# io-board-b-2.net
KiCad netlist of a schematic drawn in EAGLE
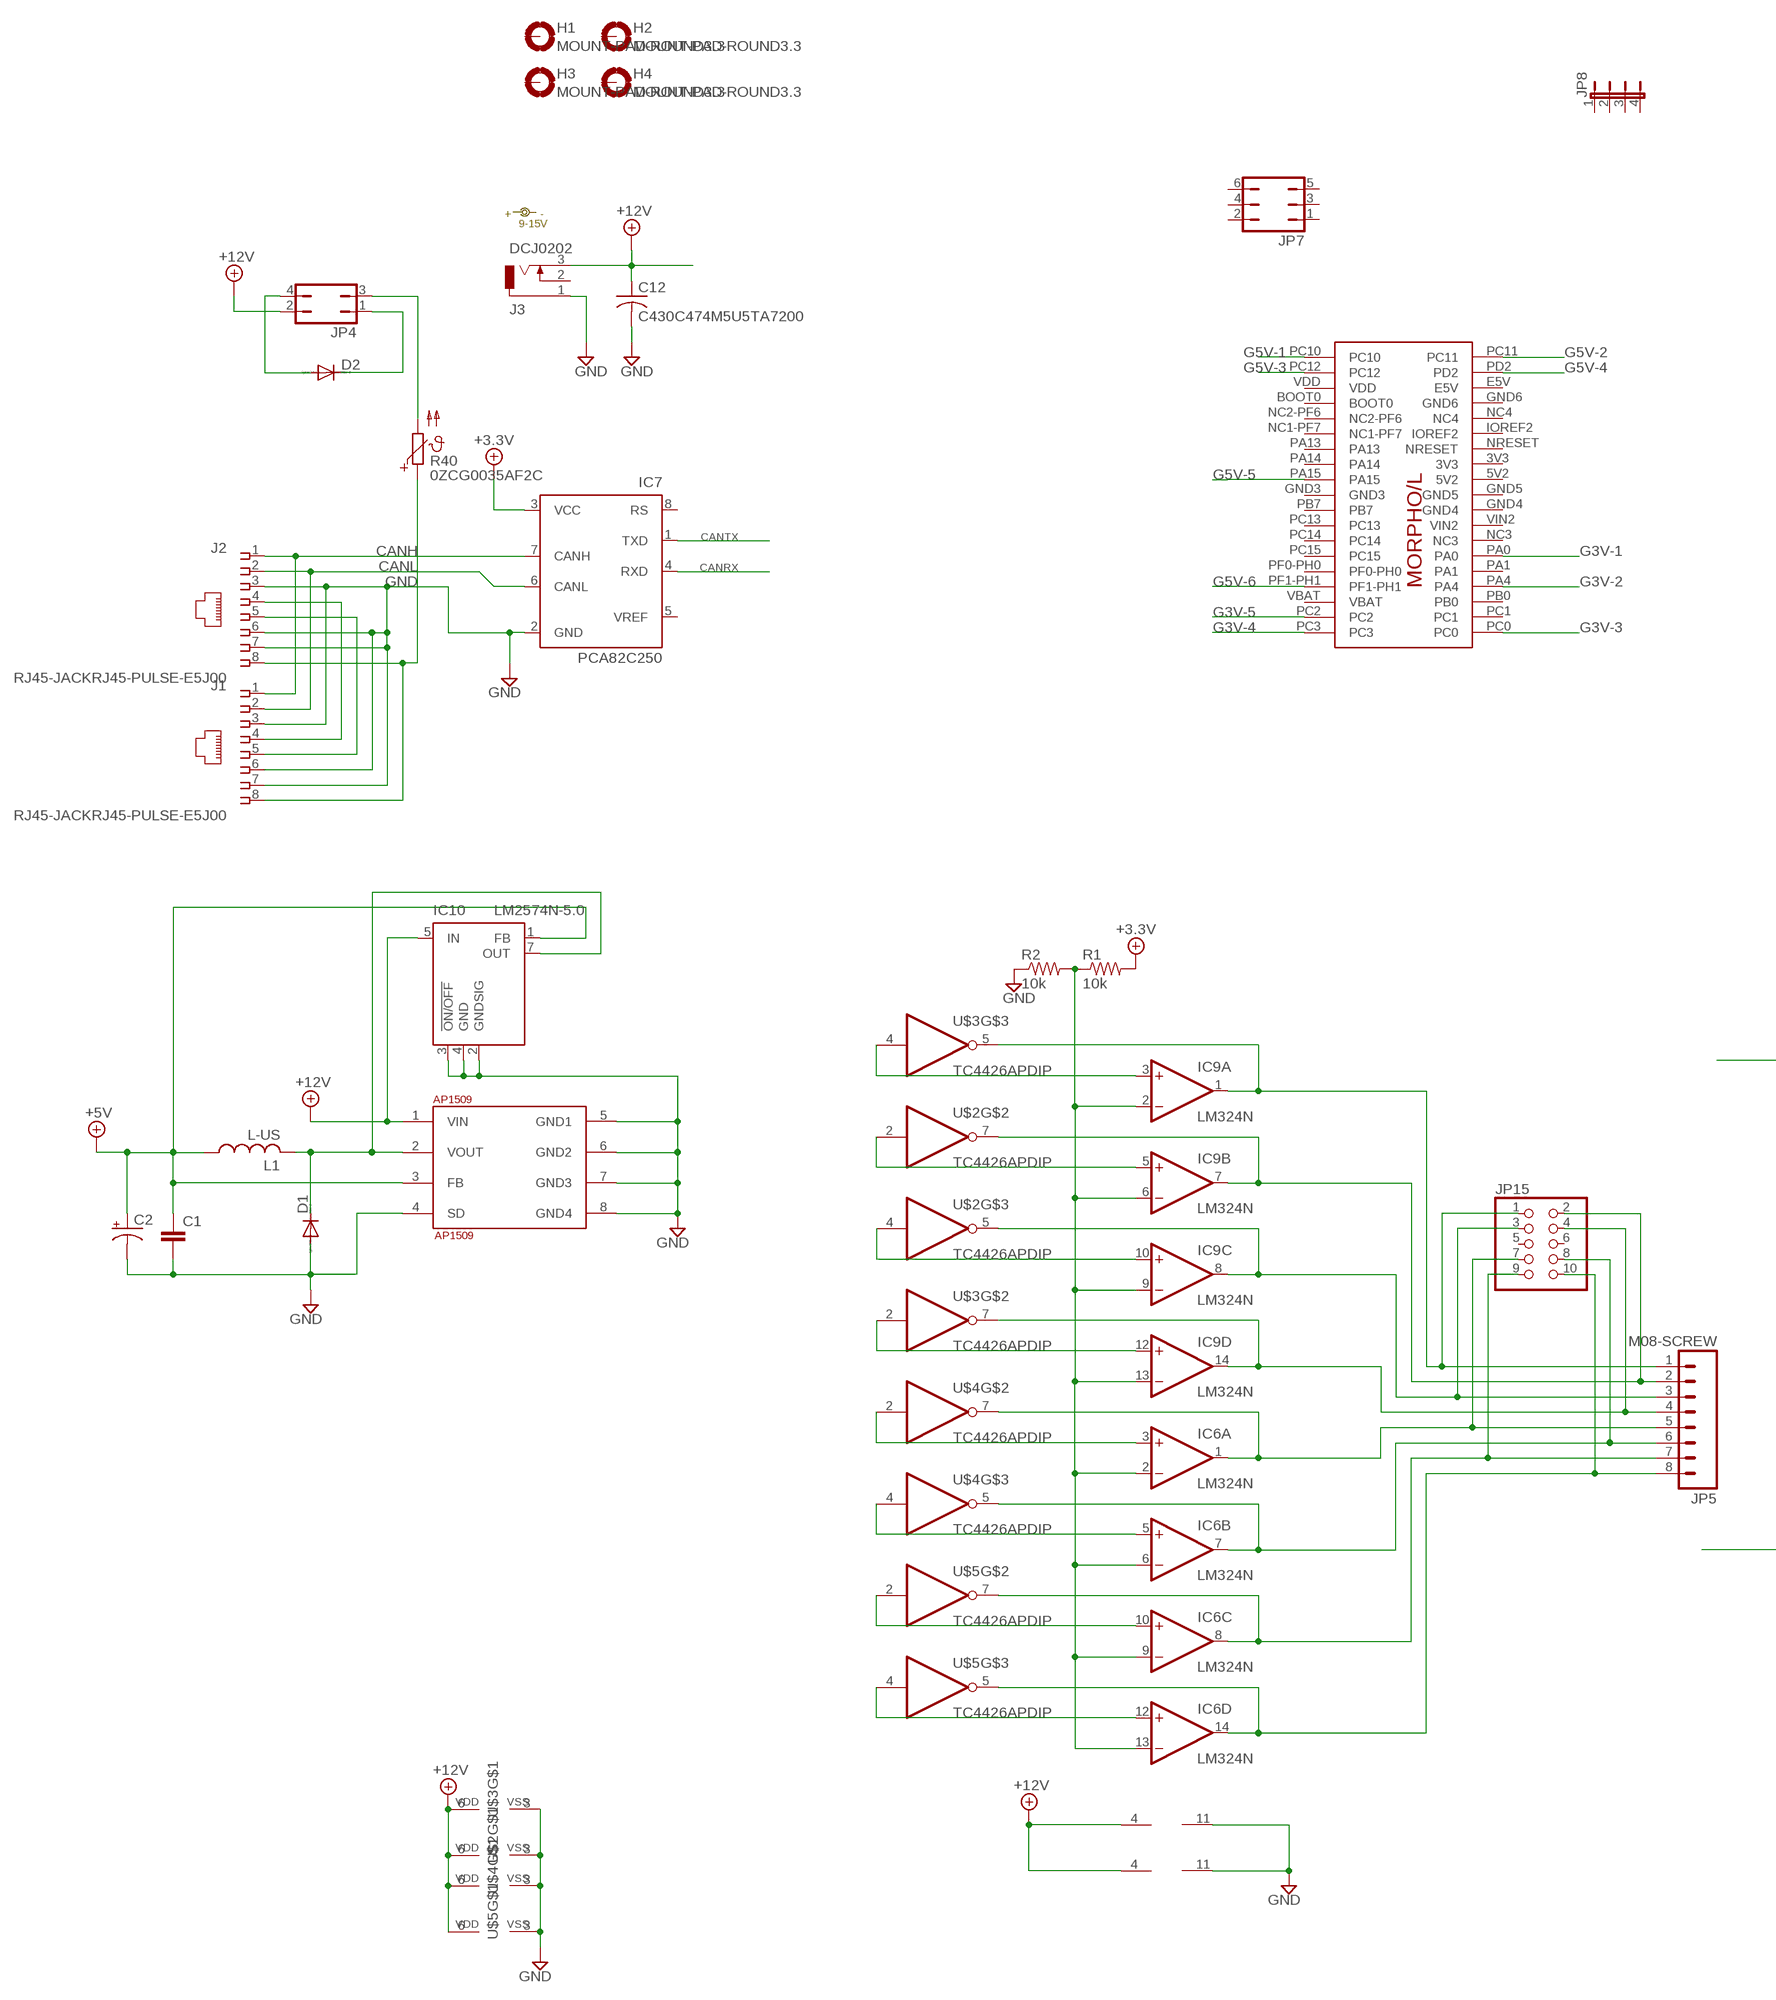
[diagram p0: schematic, sheet 1, part 1 of 2]
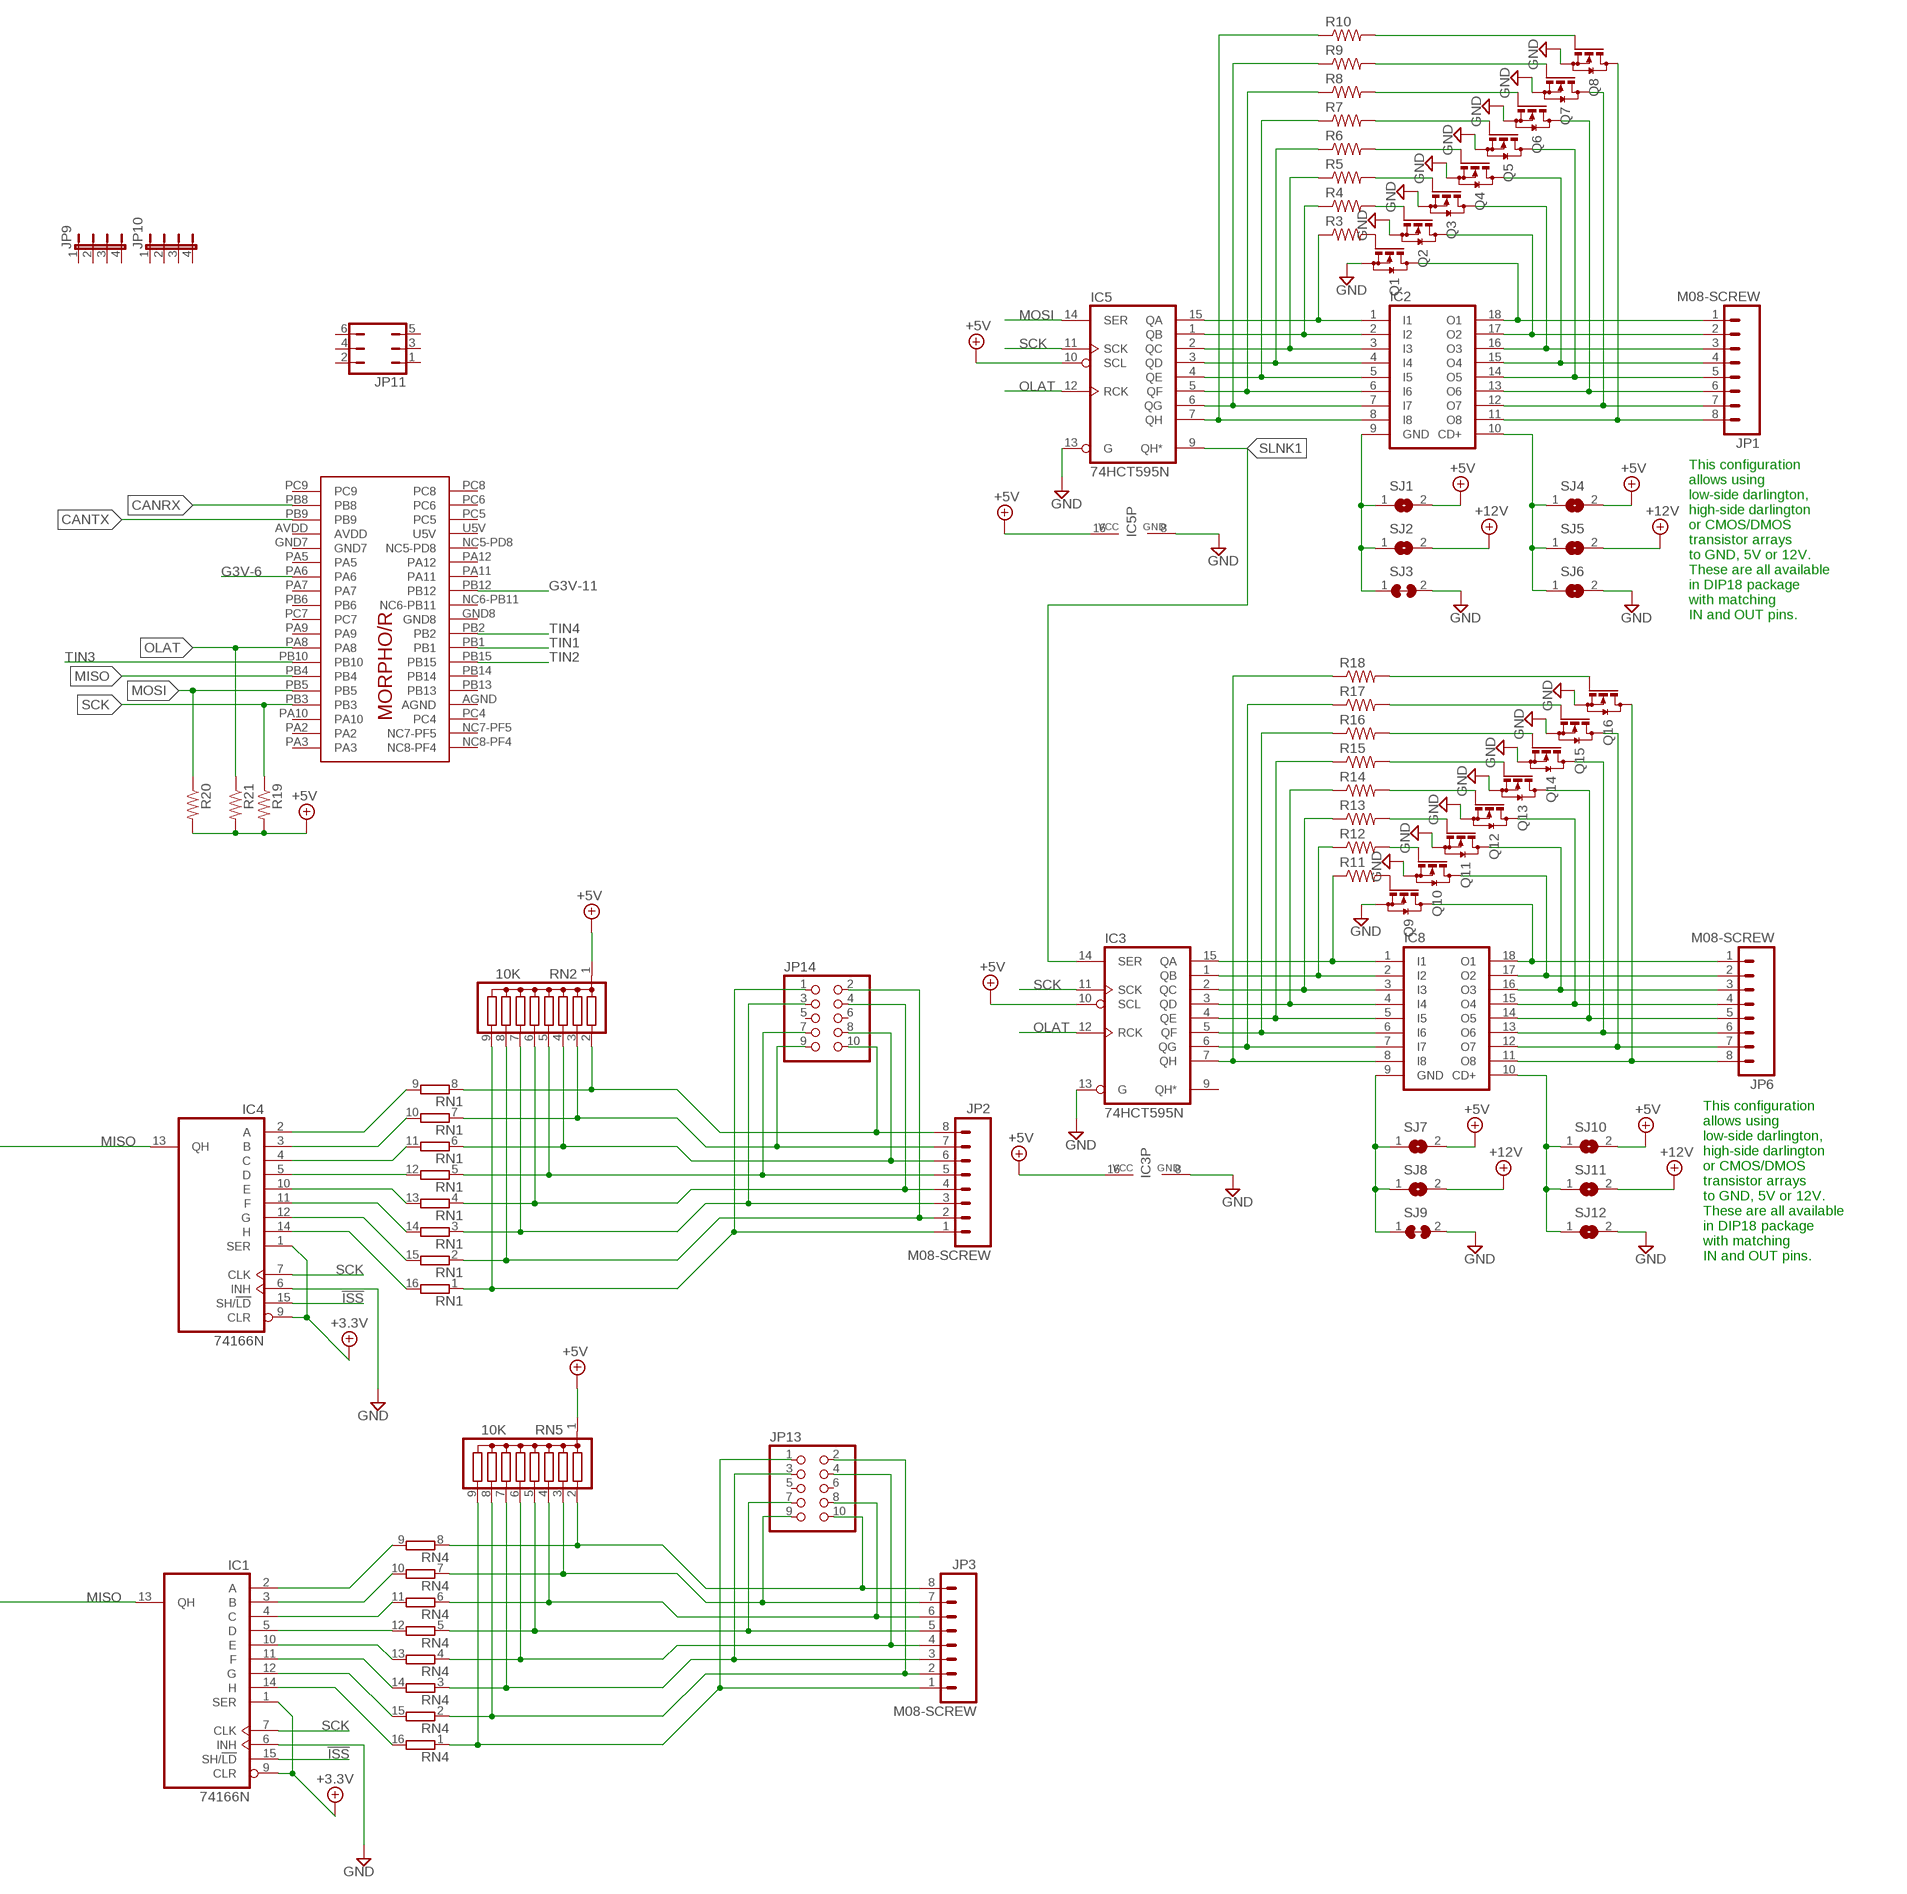
[diagram p1: schematic, sheet 1, part 2 of 2]

(export (version "E")
  (design (tool "Eeschema 10.0.6"))
  (components
    (comp (ref "+12V")
      (value "9-15V")
      (footprint "eagle-import:POWER_USAGE")
      (libsource (lib "eagle-import") (part "DOC-POWER_LABEL"))
    )
    (comp (ref "AP1509")
      (value "AP1509")
      (footprint "eagle-import:SO-08")
      (libsource (lib "eagle-import") (part "AP1509"))
    )
    (comp (ref "C1")
      (value "C-EUC1206")
      (footprint "eagle-import:C1206")
      (libsource (lib "eagle-import") (part "C-EUC1206"))
    )
    (comp (ref "C2")
      (value "CPOL-USE2.5-5")
      (footprint "eagle-import:E2,5-5")
      (libsource (lib "eagle-import") (part "CPOL-USE2.5-5"))
    )
    (comp (ref "C12")
      (value "C430C474M5U5TA7200")
      (footprint "eagle-import:C075-032X103")
      (libsource (lib "eagle-import") (part "C-US075-032X103"))
    )
    (comp (ref "D1")
      (value "DIODE-DO41-7.6")
      (footprint "eagle-import:DO41-7.6")
      (libsource (lib "eagle-import") (part "DIODE-DO41-7.6"))
    )
    (comp (ref "D2")
      (value "DIODE-DO41-7.6")
      (footprint "eagle-import:DO41-7.6")
      (libsource (lib "eagle-import") (part "DIODE-DO41-7.6"))
    )
    (comp (ref "H1")
      (value "MOUNT-PAD-ROUND3.3")
      (footprint "eagle-import:3,3-PAD")
      (libsource (lib "eagle-import") (part "MOUNT-PAD-ROUND3.3"))
    )
    (comp (ref "H2")
      (value "MOUNT-PAD-ROUND3.3")
      (footprint "eagle-import:3,3-PAD")
      (libsource (lib "eagle-import") (part "MOUNT-PAD-ROUND3.3"))
    )
    (comp (ref "H3")
      (value "MOUNT-PAD-ROUND3.3")
      (footprint "eagle-import:3,3-PAD")
      (libsource (lib "eagle-import") (part "MOUNT-PAD-ROUND3.3"))
    )
    (comp (ref "H4")
      (value "MOUNT-PAD-ROUND3.3")
      (footprint "eagle-import:3,3-PAD")
      (libsource (lib "eagle-import") (part "MOUNT-PAD-ROUND3.3"))
    )
    (comp (ref "IC1")
      (value "74166N")
      (footprint "eagle-import:DIL16")
      (libsource (lib "eagle-import") (part "74166N"))
    )
    (comp (ref "IC2")
      (value "ULN2803A")
      (footprint "eagle-import:DIL18-THIN")
      (libsource (lib "eagle-import") (part "ULN2803A"))
    )
    (comp (ref "IC3")
      (value "74HCT595N")
      (footprint "eagle-import:DIL16")
      (libsource (lib "eagle-import") (part "74595NHCT"))
    )
    (comp (ref "IC4")
      (value "74166N")
      (footprint "eagle-import:DIL16")
      (libsource (lib "eagle-import") (part "74166N"))
    )
    (comp (ref "IC5")
      (value "74HCT595N")
      (footprint "eagle-import:DIL16")
      (libsource (lib "eagle-import") (part "74595NHCT"))
    )
    (comp (ref "IC6")
      (value "LM324N")
      (footprint "eagle-import:DIL14")
      (libsource (lib "eagle-import") (part "LM324N"))
    )
    (comp (ref "IC7")
      (value "PCA82C250")
      (footprint "eagle-import:DIL08")
      (libsource (lib "eagle-import") (part "PCA82C250"))
    )
    (comp (ref "IC8")
      (value "ULN2803A")
      (footprint "eagle-import:DIL18-THIN")
      (libsource (lib "eagle-import") (part "ULN2803A"))
    )
    (comp (ref "IC9")
      (value "LM324N")
      (footprint "eagle-import:DIL14")
      (libsource (lib "eagle-import") (part "LM324N"))
    )
    (comp (ref "IC10")
      (value "LM2574N-5.0")
      (footprint "eagle-import:DIL08")
      (libsource (lib "eagle-import") (part "LM2574?-N5.0"))
    )
    (comp (ref "J1")
      (value "RJ45-JACKRJ45-PULSE-E5J00")
      (footprint "eagle-import:RJ45-PULSE-E5J88")
      (libsource (lib "eagle-import") (part "RJ45-JACKRJ45-PULSE-E5J00"))
    )
    (comp (ref "J2")
      (value "RJ45-JACKRJ45-PULSE-E5J00")
      (footprint "eagle-import:RJ45-PULSE-E5J88")
      (libsource (lib "eagle-import") (part "RJ45-JACKRJ45-PULSE-E5J00"))
    )
    (comp (ref "J3")
      (value "DCJ0202")
      (footprint "eagle-import:DCJ0202")
      (libsource (lib "eagle-import") (part "DCJ0202"))
    )
    (comp (ref "JP1")
      (value "M08-SCREW")
      (footprint "eagle-import:1X08_TERMINAL")
      (libsource (lib "eagle-import") (part "M08-SCREW"))
    )
    (comp (ref "JP2")
      (value "M08-SCREW")
      (footprint "eagle-import:1X08_TERMINAL")
      (libsource (lib "eagle-import") (part "M08-SCREW"))
    )
    (comp (ref "JP3")
      (value "M08-SCREW")
      (footprint "eagle-import:1X08_TERMINAL")
      (libsource (lib "eagle-import") (part "M08-SCREW"))
    )
    (comp (ref "JP4")
      (value "JP2Q")
      (footprint "eagle-import:JP2Q")
      (libsource (lib "eagle-import") (part "JP2Q"))
    )
    (comp (ref "JP5")
      (value "M08-SCREW")
      (footprint "eagle-import:1X08_TERMINAL")
      (libsource (lib "eagle-import") (part "M08-SCREW"))
    )
    (comp (ref "JP6")
      (value "M08-SCREW")
      (footprint "eagle-import:1X08_TERMINAL")
      (libsource (lib "eagle-import") (part "M08-SCREW"))
    )
    (comp (ref "JP7")
      (value "JP3Q")
      (footprint "eagle-import:JP3Q")
      (libsource (lib "eagle-import") (part "JP3Q"))
    )
    (comp (ref "JP8")
      (value "JP4-FLAT")
      (footprint "eagle-import:JP4F")
      (libsource (lib "eagle-import") (part "JP4-FLAT"))
    )
    (comp (ref "JP9")
      (value "JP4-FLAT")
      (footprint "eagle-import:JP4F")
      (libsource (lib "eagle-import") (part "JP4-FLAT"))
    )
    (comp (ref "JP10")
      (value "JP4-FLAT")
      (footprint "eagle-import:JP4F")
      (libsource (lib "eagle-import") (part "JP4-FLAT"))
    )
    (comp (ref "JP11")
      (value "JP3Q")
      (footprint "eagle-import:JP3Q")
      (libsource (lib "eagle-import") (part "JP3Q"))
    )
    (comp (ref "JP13")
      (value "PINHD-2X5CN")
      (footprint "eagle-import:CON10M")
      (libsource (lib "eagle-import") (part "PINHD-2X5CN"))
    )
    (comp (ref "JP14")
      (value "PINHD-2X5CN")
      (footprint "eagle-import:CON10M")
      (libsource (lib "eagle-import") (part "PINHD-2X5CN"))
    )
    (comp (ref "JP15")
      (value "PINHD-2X5CN")
      (footprint "eagle-import:CON10M")
      (libsource (lib "eagle-import") (part "PINHD-2X5CN"))
    )
    (comp (ref "L1")
      (value "L-US")
      (footprint "eagle-import:L5-8,5")
      (libsource (lib "eagle-import") (part "L-US"))
    )
    (comp (ref "Q1")
      (value "BSS123")
      (footprint "eagle-import:SOT23")
      (libsource (lib "eagle-import") (part "BSS123"))
    )
    (comp (ref "Q2")
      (value "BSS123")
      (footprint "eagle-import:SOT23")
      (libsource (lib "eagle-import") (part "BSS123"))
    )
    (comp (ref "Q3")
      (value "BSS123")
      (footprint "eagle-import:SOT23")
      (libsource (lib "eagle-import") (part "BSS123"))
    )
    (comp (ref "Q4")
      (value "BSS123")
      (footprint "eagle-import:SOT23")
      (libsource (lib "eagle-import") (part "BSS123"))
    )
    (comp (ref "Q5")
      (value "BSS123")
      (footprint "eagle-import:SOT23")
      (libsource (lib "eagle-import") (part "BSS123"))
    )
    (comp (ref "Q6")
      (value "BSS123")
      (footprint "eagle-import:SOT23")
      (libsource (lib "eagle-import") (part "BSS123"))
    )
    (comp (ref "Q7")
      (value "BSS123")
      (footprint "eagle-import:SOT23")
      (libsource (lib "eagle-import") (part "BSS123"))
    )
    (comp (ref "Q8")
      (value "BSS123")
      (footprint "eagle-import:SOT23")
      (libsource (lib "eagle-import") (part "BSS123"))
    )
    (comp (ref "Q9")
      (value "BSS123")
      (footprint "eagle-import:SOT23")
      (libsource (lib "eagle-import") (part "BSS123"))
    )
    (comp (ref "Q10")
      (value "BSS123")
      (footprint "eagle-import:SOT23")
      (libsource (lib "eagle-import") (part "BSS123"))
    )
    (comp (ref "Q11")
      (value "BSS123")
      (footprint "eagle-import:SOT23")
      (libsource (lib "eagle-import") (part "BSS123"))
    )
    (comp (ref "Q12")
      (value "BSS123")
      (footprint "eagle-import:SOT23")
      (libsource (lib "eagle-import") (part "BSS123"))
    )
    (comp (ref "Q13")
      (value "BSS123")
      (footprint "eagle-import:SOT23")
      (libsource (lib "eagle-import") (part "BSS123"))
    )
    (comp (ref "Q14")
      (value "BSS123")
      (footprint "eagle-import:SOT23")
      (libsource (lib "eagle-import") (part "BSS123"))
    )
    (comp (ref "Q15")
      (value "BSS123")
      (footprint "eagle-import:SOT23")
      (libsource (lib "eagle-import") (part "BSS123"))
    )
    (comp (ref "Q16")
      (value "BSS123")
      (footprint "eagle-import:SOT23")
      (libsource (lib "eagle-import") (part "BSS123"))
    )
    (comp (ref "R1")
      (value "10k")
      (footprint "eagle-import:R1206")
      (libsource (lib "eagle-import") (part "R-US_R1206"))
    )
    (comp (ref "R2")
      (value "10k")
      (footprint "eagle-import:R1206")
      (libsource (lib "eagle-import") (part "R-US_R1206"))
    )
    (comp (ref "R3")
      (value "R-US_R0603")
      (footprint "eagle-import:R0603")
      (libsource (lib "eagle-import") (part "R-US_R0603"))
    )
    (comp (ref "R4")
      (value "R-US_R0603")
      (footprint "eagle-import:R0603")
      (libsource (lib "eagle-import") (part "R-US_R0603"))
    )
    (comp (ref "R5")
      (value "R-US_R0603")
      (footprint "eagle-import:R0603")
      (libsource (lib "eagle-import") (part "R-US_R0603"))
    )
    (comp (ref "R6")
      (value "R-US_R0603")
      (footprint "eagle-import:R0603")
      (libsource (lib "eagle-import") (part "R-US_R0603"))
    )
    (comp (ref "R7")
      (value "R-US_R0603")
      (footprint "eagle-import:R0603")
      (libsource (lib "eagle-import") (part "R-US_R0603"))
    )
    (comp (ref "R8")
      (value "R-US_R0603")
      (footprint "eagle-import:R0603")
      (libsource (lib "eagle-import") (part "R-US_R0603"))
    )
    (comp (ref "R9")
      (value "R-US_R0603")
      (footprint "eagle-import:R0603")
      (libsource (lib "eagle-import") (part "R-US_R0603"))
    )
    (comp (ref "R10")
      (value "R-US_R0603")
      (footprint "eagle-import:R0603")
      (libsource (lib "eagle-import") (part "R-US_R0603"))
    )
    (comp (ref "R11")
      (value "R-US_R0603")
      (footprint "eagle-import:R0603")
      (libsource (lib "eagle-import") (part "R-US_R0603"))
    )
    (comp (ref "R12")
      (value "R-US_R0603")
      (footprint "eagle-import:R0603")
      (libsource (lib "eagle-import") (part "R-US_R0603"))
    )
    (comp (ref "R13")
      (value "R-US_R0603")
      (footprint "eagle-import:R0603")
      (libsource (lib "eagle-import") (part "R-US_R0603"))
    )
    (comp (ref "R14")
      (value "R-US_R0603")
      (footprint "eagle-import:R0603")
      (libsource (lib "eagle-import") (part "R-US_R0603"))
    )
    (comp (ref "R15")
      (value "R-US_R0603")
      (footprint "eagle-import:R0603")
      (libsource (lib "eagle-import") (part "R-US_R0603"))
    )
    (comp (ref "R16")
      (value "R-US_R0603")
      (footprint "eagle-import:R0603")
      (libsource (lib "eagle-import") (part "R-US_R0603"))
    )
    (comp (ref "R17")
      (value "R-US_R0603")
      (footprint "eagle-import:R0603")
      (libsource (lib "eagle-import") (part "R-US_R0603"))
    )
    (comp (ref "R18")
      (value "R-US_R0603")
      (footprint "eagle-import:R0603")
      (libsource (lib "eagle-import") (part "R-US_R0603"))
    )
    (comp (ref "R19")
      (value "R-US_R0805")
      (footprint "eagle-import:R0805")
      (libsource (lib "eagle-import") (part "rcl_334_R-US_R0805"))
    )
    (comp (ref "R20")
      (value "R-US_R0805")
      (footprint "eagle-import:R0805")
      (libsource (lib "eagle-import") (part "rcl_334_R-US_R0805"))
    )
    (comp (ref "R21")
      (value "R-US_R0805")
      (footprint "eagle-import:R0805")
      (libsource (lib "eagle-import") (part "rcl_334_R-US_R0805"))
    )
    (comp (ref "R40")
      (value "0ZCG0035AF2C")
      (footprint "eagle-import:PTC1812")
      (libsource (lib "eagle-import") (part "PTC_1812"))
    )
    (comp (ref "RN1")
      (value "8R-P")
      (footprint "eagle-import:DIL16")
      (libsource (lib "eagle-import") (part "8R-P"))
    )
    (comp (ref "RN2")
      (value "10K")
      (footprint "eagle-import:SIL9")
      (libsource (lib "eagle-import") (part "G08R"))
    )
    (comp (ref "RN4")
      (value "8R-P")
      (footprint "eagle-import:DIL16")
      (libsource (lib "eagle-import") (part "8R-P"))
    )
    (comp (ref "RN5")
      (value "10K")
      (footprint "eagle-import:SIL9")
      (libsource (lib "eagle-import") (part "G08R"))
    )
    (comp (ref "SJ1")
      (value "SJ")
      (footprint "eagle-import:SJ-RND")
      (libsource (lib "eagle-import") (part "SJ"))
    )
    (comp (ref "SJ2")
      (value "SJ")
      (footprint "eagle-import:SJ-RND")
      (libsource (lib "eagle-import") (part "SJ"))
    )
    (comp (ref "SJ3")
      (value "SJ-C")
      (footprint "eagle-import:SJW-C")
      (libsource (lib "eagle-import") (part "SJ-C"))
    )
    (comp (ref "SJ4")
      (value "SJ")
      (footprint "eagle-import:SJ-RND")
      (libsource (lib "eagle-import") (part "SJ"))
    )
    (comp (ref "SJ5")
      (value "SJ")
      (footprint "eagle-import:SJ-RND")
      (libsource (lib "eagle-import") (part "SJ"))
    )
    (comp (ref "SJ6")
      (value "SJ")
      (footprint "eagle-import:SJ-RND")
      (libsource (lib "eagle-import") (part "SJ"))
    )
    (comp (ref "SJ7")
      (value "SJ")
      (footprint "eagle-import:SJ-RND")
      (libsource (lib "eagle-import") (part "SJ"))
    )
    (comp (ref "SJ8")
      (value "SJ")
      (footprint "eagle-import:SJ-RND")
      (libsource (lib "eagle-import") (part "SJ"))
    )
    (comp (ref "SJ9")
      (value "SJ-C")
      (footprint "eagle-import:SJW-C")
      (libsource (lib "eagle-import") (part "SJ-C"))
    )
    (comp (ref "SJ10")
      (value "SJ")
      (footprint "eagle-import:SJ-RND")
      (libsource (lib "eagle-import") (part "SJ"))
    )
    (comp (ref "SJ11")
      (value "SJ")
      (footprint "eagle-import:SJ-RND")
      (libsource (lib "eagle-import") (part "SJ"))
    )
    (comp (ref "SJ12")
      (value "SJ")
      (footprint "eagle-import:SJ-RND")
      (libsource (lib "eagle-import") (part "SJ"))
    )
    (comp (ref "U$1")
      (value "NUCLEO_64_GENERIC")
      (footprint "eagle-import:NUCLEO_BRD_BASE64")
      (libsource (lib "eagle-import") (part "NUCLEO_64_GENERIC"))
    )
    (comp (ref "U$2")
      (value "TC4426APDIP")
      (footprint "eagle-import:DIL08-LONG")
      (libsource (lib "eagle-import") (part "TC4426APDIP"))
    )
    (comp (ref "U$3")
      (value "TC4426APDIP")
      (footprint "eagle-import:DIL08-LONG")
      (libsource (lib "eagle-import") (part "TC4426APDIP"))
    )
    (comp (ref "U$4")
      (value "TC4426APDIP")
      (footprint "eagle-import:DIL08-LONG")
      (libsource (lib "eagle-import") (part "TC4426APDIP"))
    )
    (comp (ref "U$5")
      (value "TC4426APDIP")
      (footprint "eagle-import:DIL08-LONG")
      (libsource (lib "eagle-import") (part "TC4426APDIP"))
    )
  )
  (nets
    (net (code "1") (name "+3.3V") (class "Default")
      (node (ref "IC1") (pin "1") (pinfunction "SER_1") (pintype "input"))
      (node (ref "IC1") (pin "9") (pinfunction "CLR_9") (pintype "input"))
      (node (ref "IC4") (pin "1") (pinfunction "SER_1") (pintype "input"))
      (node (ref "IC4") (pin "9") (pinfunction "CLR_9") (pintype "input"))
      (node (ref "IC7") (pin "3") (pinfunction "VCC_3") (pintype "power_in"))
      (node (ref "R1") (pin "2") (pinfunction "2_2") (pintype "passive"))
    )
    (net (code "2") (name "+5V") (class "Default")
      (node (ref "AP1509") (pin "3") (pinfunction "FB_3") (pintype "bidirectional"))
      (node (ref "C1") (pin "1") (pinfunction "1_1") (pintype "passive"))
      (node (ref "C2") (pin "+") (pinfunction "+_+") (pintype "passive"))
      (node (ref "IC10") (pin "1") (pinfunction "FB_1") (pintype "input"))
      (node (ref "IC3") (pin "10") (pinfunction "SCL_10") (pintype "input"))
      (node (ref "IC3") (pin "16") (pinfunction "VCC_16") (pintype "power_in"))
      (node (ref "IC5") (pin "10") (pinfunction "SCL_10") (pintype "input"))
      (node (ref "IC5") (pin "16") (pinfunction "VCC_16") (pintype "power_in"))
      (node (ref "L1") (pin "1") (pinfunction "1_1") (pintype "passive"))
      (node (ref "R19") (pin "2") (pinfunction "2_2") (pintype "passive"))
      (node (ref "R20") (pin "2") (pinfunction "2_2") (pintype "passive"))
      (node (ref "R21") (pin "2") (pinfunction "2_2") (pintype "passive"))
      (node (ref "RN2") (pin "1") (pinfunction "1_1") (pintype "passive"))
      (node (ref "RN5") (pin "1") (pinfunction "1_1") (pintype "passive"))
      (node (ref "SJ1") (pin "2") (pinfunction "2_2") (pintype "passive"))
      (node (ref "SJ10") (pin "2") (pinfunction "2_2") (pintype "passive"))
      (node (ref "SJ4") (pin "2") (pinfunction "2_2") (pintype "passive"))
      (node (ref "SJ7") (pin "2") (pinfunction "2_2") (pintype "passive"))
    )
    (net (code "3") (name "+12V") (class "Default")
      (node (ref "AP1509") (pin "1") (pinfunction "VIN_1") (pintype "bidirectional"))
      (node (ref "C12") (pin "1") (pinfunction "1_1") (pintype "passive"))
      (node (ref "IC10") (pin "5") (pinfunction "IN_5") (pintype "input"))
      (node (ref "IC6") (pin "4") (pinfunction "V+_4") (pintype "power_in"))
      (node (ref "IC9") (pin "4") (pinfunction "V+_4") (pintype "power_in"))
      (node (ref "J3") (pin "3") (pinfunction "3_3") (pintype "passive"))
      (node (ref "JP4") (pin "2") (pinfunction "2_2") (pintype "passive"))
      (node (ref "SJ11") (pin "2") (pinfunction "2_2") (pintype "passive"))
      (node (ref "SJ2") (pin "2") (pinfunction "2_2") (pintype "passive"))
      (node (ref "SJ5") (pin "2") (pinfunction "2_2") (pintype "passive"))
      (node (ref "SJ8") (pin "2") (pinfunction "2_2") (pintype "passive"))
      (node (ref "U$2") (pin "6") (pinfunction "VDD_6") (pintype "power_in"))
      (node (ref "U$3") (pin "6") (pinfunction "VDD_6") (pintype "power_in"))
      (node (ref "U$4") (pin "6") (pinfunction "VDD_6") (pintype "power_in"))
      (node (ref "U$5") (pin "6") (pinfunction "VDD_6") (pintype "power_in"))
    )
    (net (code "4") (name "/3V3") (class "Default")
      (node (ref "U$1") (pin "3V3") (pinfunction "3V3_3V3") (pintype "power_in"))
    )
    (net (code "5") (name "/5V2") (class "Default")
      (node (ref "U$1") (pin "5V2") (pinfunction "5V2_5V2") (pintype "power_in"))
    )
    (net (code "6") (name "/AGND") (class "Default")
      (node (ref "U$1") (pin "AGND") (pinfunction "AGND_AGND") (pintype "power_in"))
    )
    (net (code "7") (name "/AVDD") (class "Default")
      (node (ref "U$1") (pin "AVDD") (pinfunction "AVDD_AVDD") (pintype "power_in"))
    )
    (net (code "8") (name "/CANH") (class "Default")
      (node (ref "IC7") (pin "7") (pinfunction "CANH_7") (pintype "bidirectional"))
      (node (ref "J1") (pin "1") (pinfunction "1_1") (pintype "passive"))
      (node (ref "J2") (pin "1") (pinfunction "1_1") (pintype "passive"))
    )
    (net (code "9") (name "/CANL") (class "Default")
      (node (ref "IC7") (pin "6") (pinfunction "CANL_6") (pintype "bidirectional"))
      (node (ref "J1") (pin "2") (pinfunction "2_2") (pintype "passive"))
      (node (ref "J2") (pin "2") (pinfunction "2_2") (pintype "passive"))
    )
    (net (code "10") (name "/E5V") (class "Default")
      (node (ref "U$1") (pin "E5V") (pinfunction "E5V_E5V") (pintype "power_in"))
    )
    (net (code "11") (name "/G3V-1") (class "Default")
      (node (ref "U$1") (pin "PA0") (pinfunction "PA0_PA0") (pintype "bidirectional"))
    )
    (net (code "12") (name "/G3V-2") (class "Default")
      (node (ref "U$1") (pin "PA4") (pinfunction "PA4_PA4") (pintype "bidirectional"))
    )
    (net (code "13") (name "/G3V-3") (class "Default")
      (node (ref "U$1") (pin "PC0") (pinfunction "PC0_PC0") (pintype "bidirectional"))
    )
    (net (code "14") (name "/G3V-4") (class "Default")
      (node (ref "U$1") (pin "PC3") (pinfunction "PC3_PC3") (pintype "bidirectional"))
    )
    (net (code "15") (name "/G3V-5") (class "Default")
      (node (ref "U$1") (pin "PC2") (pinfunction "PC2_PC2") (pintype "bidirectional"))
    )
    (net (code "16") (name "/G3V-6") (class "Default")
      (node (ref "U$1") (pin "PA6") (pinfunction "PA6_PA6") (pintype "bidirectional"))
    )
    (net (code "17") (name "/G3V-11") (class "Default")
      (node (ref "U$1") (pin "PB12") (pinfunction "PB12_PB12") (pintype "bidirectional"))
    )
    (net (code "18") (name "/G5V-1") (class "Default")
      (node (ref "U$1") (pin "PC10") (pinfunction "PC10_PC10") (pintype "bidirectional"))
    )
    (net (code "19") (name "/G5V-2") (class "Default")
      (node (ref "U$1") (pin "PC11") (pinfunction "PC11_PC11") (pintype "bidirectional"))
    )
    (net (code "20") (name "/G5V-3") (class "Default")
      (node (ref "U$1") (pin "PC12") (pinfunction "PC12_PC12") (pintype "bidirectional"))
    )
    (net (code "21") (name "/G5V-4") (class "Default")
      (node (ref "U$1") (pin "PD2") (pinfunction "PD2_PD2") (pintype "bidirectional"))
    )
    (net (code "22") (name "/G5V-5") (class "Default")
      (node (ref "U$1") (pin "PA15") (pinfunction "PA15_PA15") (pintype "bidirectional"))
    )
    (net (code "23") (name "/G5V-6") (class "Default")
      (node (ref "U$1") (pin "PF1-PH1") (pinfunction "PF1-PH1_PF1-PH1") (pintype "bidirectional"))
    )
    (net (code "24") (name "/GND3") (class "Default")
      (node (ref "U$1") (pin "GND3") (pinfunction "GND3_GND3") (pintype "power_in"))
    )
    (net (code "25") (name "/GND4") (class "Default")
      (node (ref "U$1") (pin "GND4") (pinfunction "GND4_GND4") (pintype "power_in"))
    )
    (net (code "26") (name "/GND5") (class "Default")
      (node (ref "U$1") (pin "GND5") (pinfunction "GND5_GND5") (pintype "power_in"))
    )
    (net (code "27") (name "/GND6") (class "Default")
      (node (ref "U$1") (pin "GND6") (pinfunction "GND6_GND6") (pintype "power_in"))
    )
    (net (code "28") (name "/GND7") (class "Default")
      (node (ref "U$1") (pin "GND7") (pinfunction "GND7_GND7") (pintype "power_in"))
    )
    (net (code "29") (name "/GND8") (class "Default")
      (node (ref "U$1") (pin "GND8") (pinfunction "GND8_GND8") (pintype "power_in"))
    )
    (net (code "30") (name "/TIN1") (class "Default")
      (node (ref "IC9") (pin "3") (pinfunction "+IN_3") (pintype "input"))
      (node (ref "U$1") (pin "PB1") (pinfunction "PB1_PB1") (pintype "bidirectional"))
      (node (ref "U$3") (pin "4") (pinfunction "I_4") (pintype "input"))
    )
    (net (code "31") (name "/TIN2") (class "Default")
      (node (ref "IC9") (pin "5") (pinfunction "+IN_5") (pintype "input"))
      (node (ref "U$1") (pin "PB15") (pinfunction "PB15_PB15") (pintype "bidirectional"))
      (node (ref "U$2") (pin "2") (pinfunction "I_2") (pintype "input"))
    )
    (net (code "32") (name "/TIN3") (class "Default")
      (node (ref "IC9") (pin "10") (pinfunction "+IN_10") (pintype "input"))
      (node (ref "U$1") (pin "PB10") (pinfunction "PB10_PB10") (pintype "bidirectional"))
      (node (ref "U$2") (pin "4") (pinfunction "I_4") (pintype "input"))
    )
    (net (code "33") (name "/TIN4") (class "Default")
      (node (ref "IC9") (pin "12") (pinfunction "+IN_12") (pintype "input"))
      (node (ref "U$1") (pin "PB2") (pinfunction "PB2_PB2") (pintype "bidirectional"))
      (node (ref "U$3") (pin "2") (pinfunction "I_2") (pintype "input"))
    )
    (net (code "34") (name "/U5V") (class "Default")
      (node (ref "U$1") (pin "U5V") (pinfunction "U5V_U5V") (pintype "power_in"))
    )
    (net (code "35") (name "/VBAT") (class "Default")
      (node (ref "U$1") (pin "VBAT") (pinfunction "VBAT_VBAT") (pintype "power_in"))
    )
    (net (code "36") (name "/VDD") (class "Default")
      (node (ref "U$1") (pin "VDD") (pinfunction "VDD_VDD") (pintype "power_in"))
    )
    (net (code "37") (name "/VIN2") (class "Default")
      (node (ref "U$1") (pin "VIN2") (pinfunction "VIN2_VIN2") (pintype "power_in"))
    )
    (net (code "38") (name "/~{ISS}") (class "Default")
      (node (ref "IC1") (pin "15") (pinfunction "SH/~{LD}_15") (pintype "input"))
      (node (ref "IC4") (pin "15") (pinfunction "SH/~{LD}_15") (pintype "input"))
    )
    (net (code "39") (name "CANRX") (class "Default")
      (node (ref "IC7") (pin "4") (pinfunction "RXD_4") (pintype "output"))
      (node (ref "U$1") (pin "PB8") (pinfunction "PB8_PB8") (pintype "bidirectional"))
    )
    (net (code "40") (name "CANTX") (class "Default")
      (node (ref "IC7") (pin "1") (pinfunction "TXD_1") (pintype "input"))
      (node (ref "U$1") (pin "PB9") (pinfunction "PB9_PB9") (pintype "bidirectional"))
    )
    (net (code "41") (name "GND") (class "Default")
      (node (ref "AP1509") (pin "4") (pinfunction "SD_4") (pintype "bidirectional"))
      (node (ref "AP1509") (pin "5") (pinfunction "GND1_5") (pintype "power_in"))
      (node (ref "AP1509") (pin "6") (pinfunction "GND2_6") (pintype "power_in"))
      (node (ref "AP1509") (pin "7") (pinfunction "GND3_7") (pintype "power_in"))
      (node (ref "AP1509") (pin "8") (pinfunction "GND4_8") (pintype "power_in"))
      (node (ref "C1") (pin "2") (pinfunction "2_2") (pintype "passive"))
      (node (ref "C12") (pin "2") (pinfunction "2_2") (pintype "passive"))
      (node (ref "C2") (pin "-") (pinfunction "-_-") (pintype "passive"))
      (node (ref "D1") (pin "A") (pinfunction "A_A") (pintype "passive"))
      (node (ref "IC1") (pin "6") (pinfunction "INH_6") (pintype "input"))
      (node (ref "IC10") (pin "2") (pinfunction "GNDSIG_2") (pintype "input"))
      (node (ref "IC10") (pin "3") (pinfunction "~{ON/OFF}_3") (pintype "input"))
      (node (ref "IC10") (pin "4") (pinfunction "GND_4") (pintype "power_in"))
      (node (ref "IC3") (pin "13") (pinfunction "G_13") (pintype "input"))
      (node (ref "IC3") (pin "8") (pinfunction "GND_8") (pintype "power_in"))
      (node (ref "IC4") (pin "6") (pinfunction "INH_6") (pintype "input"))
      (node (ref "IC5") (pin "13") (pinfunction "G_13") (pintype "input"))
      (node (ref "IC5") (pin "8") (pinfunction "GND_8") (pintype "power_in"))
      (node (ref "IC6") (pin "11") (pinfunction "V-_11") (pintype "power_in"))
      (node (ref "IC7") (pin "2") (pinfunction "GND_2") (pintype "power_in"))
      (node (ref "IC9") (pin "11") (pinfunction "V-_11") (pintype "power_in"))
      (node (ref "J1") (pin "3") (pinfunction "3_3") (pintype "passive"))
      (node (ref "J1") (pin "6") (pinfunction "6_6") (pintype "passive"))
      (node (ref "J1") (pin "7") (pinfunction "7_7") (pintype "passive"))
      (node (ref "J2") (pin "3") (pinfunction "3_3") (pintype "passive"))
      (node (ref "J2") (pin "6") (pinfunction "6_6") (pintype "passive"))
      (node (ref "J2") (pin "7") (pinfunction "7_7") (pintype "passive"))
      (node (ref "J3") (pin "1") (pinfunction "1_1") (pintype "passive"))
      (node (ref "Q1") (pin "2") (pinfunction "S_2") (pintype "passive"))
      (node (ref "Q10") (pin "2") (pinfunction "S_2") (pintype "passive"))
      (node (ref "Q11") (pin "2") (pinfunction "S_2") (pintype "passive"))
      (node (ref "Q12") (pin "2") (pinfunction "S_2") (pintype "passive"))
      (node (ref "Q13") (pin "2") (pinfunction "S_2") (pintype "passive"))
      (node (ref "Q14") (pin "2") (pinfunction "S_2") (pintype "passive"))
      (node (ref "Q15") (pin "2") (pinfunction "S_2") (pintype "passive"))
      (node (ref "Q16") (pin "2") (pinfunction "S_2") (pintype "passive"))
      (node (ref "Q2") (pin "2") (pinfunction "S_2") (pintype "passive"))
      (node (ref "Q3") (pin "2") (pinfunction "S_2") (pintype "passive"))
      (node (ref "Q4") (pin "2") (pinfunction "S_2") (pintype "passive"))
      (node (ref "Q5") (pin "2") (pinfunction "S_2") (pintype "passive"))
      (node (ref "Q6") (pin "2") (pinfunction "S_2") (pintype "passive"))
      (node (ref "Q7") (pin "2") (pinfunction "S_2") (pintype "passive"))
      (node (ref "Q8") (pin "2") (pinfunction "S_2") (pintype "passive"))
      (node (ref "Q9") (pin "2") (pinfunction "S_2") (pintype "passive"))
      (node (ref "R2") (pin "1") (pinfunction "1_1") (pintype "passive"))
      (node (ref "SJ12") (pin "2") (pinfunction "2_2") (pintype "passive"))
      (node (ref "SJ3") (pin "2") (pinfunction "2_2") (pintype "passive"))
      (node (ref "SJ6") (pin "2") (pinfunction "2_2") (pintype "passive"))
      (node (ref "SJ9") (pin "2") (pinfunction "2_2") (pintype "passive"))
      (node (ref "U$2") (pin "3") (pinfunction "VSS_3") (pintype "power_in"))
      (node (ref "U$3") (pin "3") (pinfunction "VSS_3") (pintype "power_in"))
      (node (ref "U$4") (pin "3") (pinfunction "VSS_3") (pintype "power_in"))
      (node (ref "U$5") (pin "3") (pinfunction "VSS_3") (pintype "power_in"))
    )
    (net (code "42") (name "MISO") (class "Default")
      (node (ref "IC1") (pin "13") (pinfunction "QH_13") (pintype "output"))
      (node (ref "IC4") (pin "13") (pinfunction "QH_13") (pintype "output"))
      (node (ref "U$1") (pin "PB4") (pinfunction "PB4_PB4") (pintype "bidirectional"))
    )
    (net (code "43") (name "MOSI") (class "Default")
      (node (ref "IC5") (pin "14") (pinfunction "SER_14") (pintype "input"))
      (node (ref "R20") (pin "1") (pinfunction "1_1") (pintype "passive"))
      (node (ref "U$1") (pin "PB5") (pinfunction "PB5_PB5") (pintype "bidirectional"))
    )
    (net (code "44") (name "Net-(AP1509-VOUT)") (class "Default")
      (node (ref "AP1509") (pin "2") (pinfunction "VOUT_2") (pintype "bidirectional"))
      (node (ref "D1") (pin "C") (pinfunction "C_C") (pintype "passive"))
      (node (ref "IC10") (pin "7") (pinfunction "OUT_7") (pintype "passive"))
      (node (ref "L1") (pin "2") (pinfunction "2_2") (pintype "passive"))
    )
    (net (code "45") (name "Net-(D2-PadA)") (class "Default")
      (node (ref "D2") (pin "A") (pinfunction "A_A") (pintype "passive"))
      (node (ref "JP4") (pin "4") (pinfunction "4_4") (pintype "passive"))
    )
    (net (code "46") (name "Net-(D2-PadC)") (class "Default")
      (node (ref "D2") (pin "C") (pinfunction "C_C") (pintype "passive"))
      (node (ref "JP4") (pin "1") (pinfunction "1_1") (pintype "passive"))
    )
    (net (code "47") (name "Net-(IC1A-A)") (class "Default")
      (node (ref "IC1") (pin "2") (pinfunction "A_2") (pintype "input"))
      (node (ref "RN4") (pin "9") (pinfunction "2_9") (pintype "passive"))
    )
    (net (code "48") (name "Net-(IC1A-B)") (class "Default")
      (node (ref "IC1") (pin "3") (pinfunction "B_3") (pintype "input"))
      (node (ref "RN4") (pin "10") (pinfunction "2_10") (pintype "passive"))
    )
    (net (code "49") (name "Net-(IC1A-C)") (class "Default")
      (node (ref "IC1") (pin "4") (pinfunction "C_4") (pintype "input"))
      (node (ref "RN4") (pin "11") (pinfunction "2_11") (pintype "passive"))
    )
    (net (code "50") (name "Net-(IC1A-D)") (class "Default")
      (node (ref "IC1") (pin "5") (pinfunction "D_5") (pintype "input"))
      (node (ref "RN4") (pin "12") (pinfunction "2_12") (pintype "passive"))
    )
    (net (code "51") (name "Net-(IC1A-E)") (class "Default")
      (node (ref "IC1") (pin "10") (pinfunction "E_10") (pintype "input"))
      (node (ref "RN4") (pin "13") (pinfunction "2_13") (pintype "passive"))
    )
    (net (code "52") (name "Net-(IC1A-F)") (class "Default")
      (node (ref "IC1") (pin "11") (pinfunction "F_11") (pintype "input"))
      (node (ref "RN4") (pin "14") (pinfunction "2_14") (pintype "passive"))
    )
    (net (code "53") (name "Net-(IC1A-G)") (class "Default")
      (node (ref "IC1") (pin "12") (pinfunction "G_12") (pintype "input"))
      (node (ref "RN4") (pin "15") (pinfunction "2_15") (pintype "passive"))
    )
    (net (code "54") (name "Net-(IC1A-H)") (class "Default")
      (node (ref "IC1") (pin "14") (pinfunction "H_14") (pintype "input"))
      (node (ref "RN4") (pin "16") (pinfunction "2_16") (pintype "passive"))
    )
    (net (code "55") (name "Net-(IC2-CD+)") (class "Default")
      (node (ref "IC2") (pin "10") (pinfunction "CD+_10") (pintype "passive"))
      (node (ref "SJ4") (pin "1") (pinfunction "1_1") (pintype "passive"))
      (node (ref "SJ5") (pin "1") (pinfunction "1_1") (pintype "passive"))
      (node (ref "SJ6") (pin "1") (pinfunction "1_1") (pintype "passive"))
    )
    (net (code "56") (name "Net-(IC2-GND)") (class "Default")
      (node (ref "IC2") (pin "9") (pinfunction "GND_9") (pintype "power_in"))
      (node (ref "SJ1") (pin "1") (pinfunction "1_1") (pintype "passive"))
      (node (ref "SJ2") (pin "1") (pinfunction "1_1") (pintype "passive"))
      (node (ref "SJ3") (pin "1") (pinfunction "1_1") (pintype "passive"))
    )
    (net (code "57") (name "Net-(IC2-I1)") (class "Default")
      (node (ref "IC2") (pin "1") (pinfunction "I1_1") (pintype "input"))
      (node (ref "IC5") (pin "15") (pinfunction "QA_15") (pintype "tri_state"))
      (node (ref "R3") (pin "1") (pinfunction "1_1") (pintype "passive"))
    )
    (net (code "58") (name "Net-(IC2-I2)") (class "Default")
      (node (ref "IC2") (pin "2") (pinfunction "I2_2") (pintype "input"))
      (node (ref "IC5") (pin "1") (pinfunction "QB_1") (pintype "tri_state"))
      (node (ref "R4") (pin "1") (pinfunction "1_1") (pintype "passive"))
    )
    (net (code "59") (name "Net-(IC2-I3)") (class "Default")
      (node (ref "IC2") (pin "3") (pinfunction "I3_3") (pintype "input"))
      (node (ref "IC5") (pin "2") (pinfunction "QC_2") (pintype "tri_state"))
      (node (ref "R5") (pin "1") (pinfunction "1_1") (pintype "passive"))
    )
    (net (code "60") (name "Net-(IC2-I4)") (class "Default")
      (node (ref "IC2") (pin "4") (pinfunction "I4_4") (pintype "input"))
      (node (ref "IC5") (pin "3") (pinfunction "QD_3") (pintype "tri_state"))
      (node (ref "R6") (pin "1") (pinfunction "1_1") (pintype "passive"))
    )
    (net (code "61") (name "Net-(IC2-I5)") (class "Default")
      (node (ref "IC2") (pin "5") (pinfunction "I5_5") (pintype "input"))
      (node (ref "IC5") (pin "4") (pinfunction "QE_4") (pintype "tri_state"))
      (node (ref "R7") (pin "1") (pinfunction "1_1") (pintype "passive"))
    )
    (net (code "62") (name "Net-(IC2-I6)") (class "Default")
      (node (ref "IC2") (pin "6") (pinfunction "I6_6") (pintype "input"))
      (node (ref "IC5") (pin "5") (pinfunction "QF_5") (pintype "tri_state"))
      (node (ref "R8") (pin "1") (pinfunction "1_1") (pintype "passive"))
    )
    (net (code "63") (name "Net-(IC2-I7)") (class "Default")
      (node (ref "IC2") (pin "7") (pinfunction "I7_7") (pintype "input"))
      (node (ref "IC5") (pin "6") (pinfunction "QG_6") (pintype "tri_state"))
      (node (ref "R9") (pin "1") (pinfunction "1_1") (pintype "passive"))
    )
    (net (code "64") (name "Net-(IC2-I8)") (class "Default")
      (node (ref "IC2") (pin "8") (pinfunction "I8_8") (pintype "input"))
      (node (ref "IC5") (pin "7") (pinfunction "QH_7") (pintype "tri_state"))
      (node (ref "R10") (pin "1") (pinfunction "1_1") (pintype "passive"))
    )
    (net (code "65") (name "Net-(IC2-O1)") (class "Default")
      (node (ref "IC2") (pin "18") (pinfunction "O1_18") (pintype "open_collector"))
      (node (ref "JP1") (pin "1") (pinfunction "1_1") (pintype "passive"))
      (node (ref "Q1") (pin "3") (pinfunction "D_3") (pintype "passive"))
    )
    (net (code "66") (name "Net-(IC2-O2)") (class "Default")
      (node (ref "IC2") (pin "17") (pinfunction "O2_17") (pintype "open_collector"))
      (node (ref "JP1") (pin "2") (pinfunction "2_2") (pintype "passive"))
      (node (ref "Q2") (pin "3") (pinfunction "D_3") (pintype "passive"))
    )
    (net (code "67") (name "Net-(IC2-O3)") (class "Default")
      (node (ref "IC2") (pin "16") (pinfunction "O3_16") (pintype "open_collector"))
      (node (ref "JP1") (pin "3") (pinfunction "3_3") (pintype "passive"))
      (node (ref "Q3") (pin "3") (pinfunction "D_3") (pintype "passive"))
    )
    (net (code "68") (name "Net-(IC2-O4)") (class "Default")
      (node (ref "IC2") (pin "15") (pinfunction "O4_15") (pintype "open_collector"))
      (node (ref "JP1") (pin "4") (pinfunction "4_4") (pintype "passive"))
      (node (ref "Q4") (pin "3") (pinfunction "D_3") (pintype "passive"))
    )
    (net (code "69") (name "Net-(IC2-O5)") (class "Default")
      (node (ref "IC2") (pin "14") (pinfunction "O5_14") (pintype "open_collector"))
      (node (ref "JP1") (pin "5") (pinfunction "5_5") (pintype "passive"))
      (node (ref "Q5") (pin "3") (pinfunction "D_3") (pintype "passive"))
    )
    (net (code "70") (name "Net-(IC2-O6)") (class "Default")
      (node (ref "IC2") (pin "13") (pinfunction "O6_13") (pintype "open_collector"))
      (node (ref "JP1") (pin "6") (pinfunction "6_6") (pintype "passive"))
      (node (ref "Q6") (pin "3") (pinfunction "D_3") (pintype "passive"))
    )
    (net (code "71") (name "Net-(IC2-O7)") (class "Default")
      (node (ref "IC2") (pin "12") (pinfunction "O7_12") (pintype "open_collector"))
      (node (ref "JP1") (pin "7") (pinfunction "7_7") (pintype "passive"))
      (node (ref "Q7") (pin "3") (pinfunction "D_3") (pintype "passive"))
    )
    (net (code "72") (name "Net-(IC2-O8)") (class "Default")
      (node (ref "IC2") (pin "11") (pinfunction "O8_11") (pintype "open_collector"))
      (node (ref "JP1") (pin "8") (pinfunction "8_8") (pintype "passive"))
      (node (ref "Q8") (pin "3") (pinfunction "D_3") (pintype "passive"))
    )
    (net (code "73") (name "Net-(IC3A-QA)") (class "Default")
      (node (ref "IC3") (pin "15") (pinfunction "QA_15") (pintype "tri_state"))
      (node (ref "IC8") (pin "1") (pinfunction "I1_1") (pintype "input"))
      (node (ref "R11") (pin "1") (pinfunction "1_1") (pintype "passive"))
    )
    (net (code "74") (name "Net-(IC3A-QB)") (class "Default")
      (node (ref "IC3") (pin "1") (pinfunction "QB_1") (pintype "tri_state"))
      (node (ref "IC8") (pin "2") (pinfunction "I2_2") (pintype "input"))
      (node (ref "R12") (pin "1") (pinfunction "1_1") (pintype "passive"))
    )
    (net (code "75") (name "Net-(IC3A-QC)") (class "Default")
      (node (ref "IC3") (pin "2") (pinfunction "QC_2") (pintype "tri_state"))
      (node (ref "IC8") (pin "3") (pinfunction "I3_3") (pintype "input"))
      (node (ref "R13") (pin "1") (pinfunction "1_1") (pintype "passive"))
    )
    (net (code "76") (name "Net-(IC3A-QD)") (class "Default")
      (node (ref "IC3") (pin "3") (pinfunction "QD_3") (pintype "tri_state"))
      (node (ref "IC8") (pin "4") (pinfunction "I4_4") (pintype "input"))
      (node (ref "R14") (pin "1") (pinfunction "1_1") (pintype "passive"))
    )
    (net (code "77") (name "Net-(IC3A-QE)") (class "Default")
      (node (ref "IC3") (pin "4") (pinfunction "QE_4") (pintype "tri_state"))
      (node (ref "IC8") (pin "5") (pinfunction "I5_5") (pintype "input"))
      (node (ref "R15") (pin "1") (pinfunction "1_1") (pintype "passive"))
    )
    (net (code "78") (name "Net-(IC3A-QF)") (class "Default")
      (node (ref "IC3") (pin "5") (pinfunction "QF_5") (pintype "tri_state"))
      (node (ref "IC8") (pin "6") (pinfunction "I6_6") (pintype "input"))
      (node (ref "R16") (pin "1") (pinfunction "1_1") (pintype "passive"))
    )
    (net (code "79") (name "Net-(IC3A-QG)") (class "Default")
      (node (ref "IC3") (pin "6") (pinfunction "QG_6") (pintype "tri_state"))
      (node (ref "IC8") (pin "7") (pinfunction "I7_7") (pintype "input"))
      (node (ref "R17") (pin "1") (pinfunction "1_1") (pintype "passive"))
    )
    (net (code "80") (name "Net-(IC3A-QH)") (class "Default")
      (node (ref "IC3") (pin "7") (pinfunction "QH_7") (pintype "tri_state"))
      (node (ref "IC8") (pin "8") (pinfunction "I8_8") (pintype "input"))
      (node (ref "R18") (pin "1") (pinfunction "1_1") (pintype "passive"))
    )
    (net (code "81") (name "Net-(IC4A-A)") (class "Default")
      (node (ref "IC4") (pin "2") (pinfunction "A_2") (pintype "input"))
      (node (ref "RN1") (pin "9") (pinfunction "2_9") (pintype "passive"))
    )
    (net (code "82") (name "Net-(IC4A-B)") (class "Default")
      (node (ref "IC4") (pin "3") (pinfunction "B_3") (pintype "input"))
      (node (ref "RN1") (pin "10") (pinfunction "2_10") (pintype "passive"))
    )
    (net (code "83") (name "Net-(IC4A-C)") (class "Default")
      (node (ref "IC4") (pin "4") (pinfunction "C_4") (pintype "input"))
      (node (ref "RN1") (pin "11") (pinfunction "2_11") (pintype "passive"))
    )
    (net (code "84") (name "Net-(IC4A-D)") (class "Default")
      (node (ref "IC4") (pin "5") (pinfunction "D_5") (pintype "input"))
      (node (ref "RN1") (pin "12") (pinfunction "2_12") (pintype "passive"))
    )
    (net (code "85") (name "Net-(IC4A-E)") (class "Default")
      (node (ref "IC4") (pin "10") (pinfunction "E_10") (pintype "input"))
      (node (ref "RN1") (pin "13") (pinfunction "2_13") (pintype "passive"))
    )
    (net (code "86") (name "Net-(IC4A-F)") (class "Default")
      (node (ref "IC4") (pin "11") (pinfunction "F_11") (pintype "input"))
      (node (ref "RN1") (pin "14") (pinfunction "2_14") (pintype "passive"))
    )
    (net (code "87") (name "Net-(IC4A-G)") (class "Default")
      (node (ref "IC4") (pin "12") (pinfunction "G_12") (pintype "input"))
      (node (ref "RN1") (pin "15") (pinfunction "2_15") (pintype "passive"))
    )
    (net (code "88") (name "Net-(IC4A-H)") (class "Default")
      (node (ref "IC4") (pin "14") (pinfunction "H_14") (pintype "input"))
      (node (ref "RN1") (pin "16") (pinfunction "2_16") (pintype "passive"))
    )
    (net (code "89") (name "Net-(IC6A-+IN)") (class "Default")
      (node (ref "IC6") (pin "3") (pinfunction "+IN_3") (pintype "input"))
      (node (ref "U$4") (pin "2") (pinfunction "I_2") (pintype "input"))
    )
    (net (code "90") (name "Net-(IC6A--IN)") (class "Default")
      (node (ref "IC6") (pin "13") (pinfunction "-IN_13") (pintype "input"))
      (node (ref "IC6") (pin "2") (pinfunction "-IN_2") (pintype "input"))
      (node (ref "IC6") (pin "6") (pinfunction "-IN_6") (pintype "input"))
      (node (ref "IC6") (pin "9") (pinfunction "-IN_9") (pintype "input"))
      (node (ref "IC9") (pin "13") (pinfunction "-IN_13") (pintype "input"))
      (node (ref "IC9") (pin "2") (pinfunction "-IN_2") (pintype "input"))
      (node (ref "IC9") (pin "6") (pinfunction "-IN_6") (pintype "input"))
      (node (ref "IC9") (pin "9") (pinfunction "-IN_9") (pintype "input"))
      (node (ref "R1") (pin "1") (pinfunction "1_1") (pintype "passive"))
      (node (ref "R2") (pin "2") (pinfunction "2_2") (pintype "passive"))
    )
    (net (code "91") (name "Net-(IC6A-OUT)") (class "Default")
      (node (ref "IC6") (pin "1") (pinfunction "OUT_1") (pintype "output"))
      (node (ref "JP15") (pin "7") (pinfunction "7_7") (pintype "passive"))
      (node (ref "JP5") (pin "5") (pinfunction "5_5") (pintype "passive"))
      (node (ref "U$4") (pin "7") (pinfunction "O_7") (pintype "output"))
    )
    (net (code "92") (name "Net-(IC6B-+IN)") (class "Default")
      (node (ref "IC6") (pin "5") (pinfunction "+IN_5") (pintype "input"))
      (node (ref "U$4") (pin "4") (pinfunction "I_4") (pintype "input"))
    )
    (net (code "93") (name "Net-(IC6B-OUT)") (class "Default")
      (node (ref "IC6") (pin "7") (pinfunction "OUT_7") (pintype "output"))
      (node (ref "JP15") (pin "8") (pinfunction "8_8") (pintype "passive"))
      (node (ref "JP5") (pin "6") (pinfunction "6_6") (pintype "passive"))
      (node (ref "U$4") (pin "5") (pinfunction "O_5") (pintype "output"))
    )
    (net (code "94") (name "Net-(IC6C-+IN)") (class "Default")
      (node (ref "IC6") (pin "10") (pinfunction "+IN_10") (pintype "input"))
      (node (ref "U$5") (pin "2") (pinfunction "I_2") (pintype "input"))
    )
    (net (code "95") (name "Net-(IC6C-OUT)") (class "Default")
      (node (ref "IC6") (pin "8") (pinfunction "OUT_8") (pintype "output"))
      (node (ref "JP15") (pin "9") (pinfunction "9_9") (pintype "passive"))
      (node (ref "JP5") (pin "7") (pinfunction "7_7") (pintype "passive"))
      (node (ref "U$5") (pin "7") (pinfunction "O_7") (pintype "output"))
    )
    (net (code "96") (name "Net-(IC6D-+IN)") (class "Default")
      (node (ref "IC6") (pin "12") (pinfunction "+IN_12") (pintype "input"))
      (node (ref "U$5") (pin "4") (pinfunction "I_4") (pintype "input"))
    )
    (net (code "97") (name "Net-(IC6D-OUT)") (class "Default")
      (node (ref "IC6") (pin "14") (pinfunction "OUT_14") (pintype "output"))
      (node (ref "JP15") (pin "10") (pinfunction "10_10") (pintype "passive"))
      (node (ref "JP5") (pin "8") (pinfunction "8_8") (pintype "passive"))
      (node (ref "U$5") (pin "5") (pinfunction "O_5") (pintype "output"))
    )
    (net (code "98") (name "Net-(IC8-CD+)") (class "Default")
      (node (ref "IC8") (pin "10") (pinfunction "CD+_10") (pintype "passive"))
      (node (ref "SJ10") (pin "1") (pinfunction "1_1") (pintype "passive"))
      (node (ref "SJ11") (pin "1") (pinfunction "1_1") (pintype "passive"))
      (node (ref "SJ12") (pin "1") (pinfunction "1_1") (pintype "passive"))
    )
    (net (code "99") (name "Net-(IC8-GND)") (class "Default")
      (node (ref "IC8") (pin "9") (pinfunction "GND_9") (pintype "power_in"))
      (node (ref "SJ7") (pin "1") (pinfunction "1_1") (pintype "passive"))
      (node (ref "SJ8") (pin "1") (pinfunction "1_1") (pintype "passive"))
      (node (ref "SJ9") (pin "1") (pinfunction "1_1") (pintype "passive"))
    )
    (net (code "100") (name "Net-(IC8-O1)") (class "Default")
      (node (ref "IC8") (pin "18") (pinfunction "O1_18") (pintype "open_collector"))
      (node (ref "JP6") (pin "1") (pinfunction "1_1") (pintype "passive"))
      (node (ref "Q9") (pin "3") (pinfunction "D_3") (pintype "passive"))
    )
    (net (code "101") (name "Net-(IC8-O2)") (class "Default")
      (node (ref "IC8") (pin "17") (pinfunction "O2_17") (pintype "open_collector"))
      (node (ref "JP6") (pin "2") (pinfunction "2_2") (pintype "passive"))
      (node (ref "Q10") (pin "3") (pinfunction "D_3") (pintype "passive"))
    )
    (net (code "102") (name "Net-(IC8-O3)") (class "Default")
      (node (ref "IC8") (pin "16") (pinfunction "O3_16") (pintype "open_collector"))
      (node (ref "JP6") (pin "3") (pinfunction "3_3") (pintype "passive"))
      (node (ref "Q11") (pin "3") (pinfunction "D_3") (pintype "passive"))
    )
    (net (code "103") (name "Net-(IC8-O4)") (class "Default")
      (node (ref "IC8") (pin "15") (pinfunction "O4_15") (pintype "open_collector"))
      (node (ref "JP6") (pin "4") (pinfunction "4_4") (pintype "passive"))
      (node (ref "Q12") (pin "3") (pinfunction "D_3") (pintype "passive"))
    )
    (net (code "104") (name "Net-(IC8-O5)") (class "Default")
      (node (ref "IC8") (pin "14") (pinfunction "O5_14") (pintype "open_collector"))
      (node (ref "JP6") (pin "5") (pinfunction "5_5") (pintype "passive"))
      (node (ref "Q13") (pin "3") (pinfunction "D_3") (pintype "passive"))
    )
    (net (code "105") (name "Net-(IC8-O6)") (class "Default")
      (node (ref "IC8") (pin "13") (pinfunction "O6_13") (pintype "open_collector"))
      (node (ref "JP6") (pin "6") (pinfunction "6_6") (pintype "passive"))
      (node (ref "Q14") (pin "3") (pinfunction "D_3") (pintype "passive"))
    )
    (net (code "106") (name "Net-(IC8-O7)") (class "Default")
      (node (ref "IC8") (pin "12") (pinfunction "O7_12") (pintype "open_collector"))
      (node (ref "JP6") (pin "7") (pinfunction "7_7") (pintype "passive"))
      (node (ref "Q15") (pin "3") (pinfunction "D_3") (pintype "passive"))
    )
    (net (code "107") (name "Net-(IC8-O8)") (class "Default")
      (node (ref "IC8") (pin "11") (pinfunction "O8_11") (pintype "open_collector"))
      (node (ref "JP6") (pin "8") (pinfunction "8_8") (pintype "passive"))
      (node (ref "Q16") (pin "3") (pinfunction "D_3") (pintype "passive"))
    )
    (net (code "108") (name "Net-(IC9A-OUT)") (class "Default")
      (node (ref "IC9") (pin "1") (pinfunction "OUT_1") (pintype "output"))
      (node (ref "JP15") (pin "1") (pinfunction "1_1") (pintype "passive"))
      (node (ref "JP5") (pin "1") (pinfunction "1_1") (pintype "passive"))
      (node (ref "U$3") (pin "5") (pinfunction "O_5") (pintype "output"))
    )
    (net (code "109") (name "Net-(IC9B-OUT)") (class "Default")
      (node (ref "IC9") (pin "7") (pinfunction "OUT_7") (pintype "output"))
      (node (ref "JP15") (pin "2") (pinfunction "2_2") (pintype "passive"))
      (node (ref "JP5") (pin "2") (pinfunction "2_2") (pintype "passive"))
      (node (ref "U$2") (pin "7") (pinfunction "O_7") (pintype "output"))
    )
    (net (code "110") (name "Net-(IC9C-OUT)") (class "Default")
      (node (ref "IC9") (pin "8") (pinfunction "OUT_8") (pintype "output"))
      (node (ref "JP15") (pin "3") (pinfunction "3_3") (pintype "passive"))
      (node (ref "JP5") (pin "3") (pinfunction "3_3") (pintype "passive"))
      (node (ref "U$2") (pin "5") (pinfunction "O_5") (pintype "output"))
    )
    (net (code "111") (name "Net-(IC9D-OUT)") (class "Default")
      (node (ref "IC9") (pin "14") (pinfunction "OUT_14") (pintype "output"))
      (node (ref "JP15") (pin "4") (pinfunction "4_4") (pintype "passive"))
      (node (ref "JP5") (pin "4") (pinfunction "4_4") (pintype "passive"))
      (node (ref "U$3") (pin "7") (pinfunction "O_7") (pintype "output"))
    )
    (net (code "112") (name "Net-(J1-Pad4)") (class "Default")
      (node (ref "J1") (pin "4") (pinfunction "4_4") (pintype "passive"))
      (node (ref "J2") (pin "4") (pinfunction "4_4") (pintype "passive"))
    )
    (net (code "113") (name "Net-(J1-Pad5)") (class "Default")
      (node (ref "J1") (pin "5") (pinfunction "5_5") (pintype "passive"))
      (node (ref "J2") (pin "5") (pinfunction "5_5") (pintype "passive"))
    )
    (net (code "114") (name "Net-(J1-Pad8)") (class "Default")
      (node (ref "J1") (pin "8") (pinfunction "8_8") (pintype "passive"))
      (node (ref "J2") (pin "8") (pinfunction "8_8") (pintype "passive"))
      (node (ref "R40") (pin "1") (pinfunction "1_1") (pintype "passive"))
    )
    (net (code "115") (name "Net-(JP4-Pad3)") (class "Default")
      (node (ref "JP4") (pin "3") (pinfunction "3_3") (pintype "passive"))
      (node (ref "R40") (pin "2") (pinfunction "2_2") (pintype "passive"))
    )
    (net (code "116") (name "Net-(JP13-Pad1)") (class "Default")
      (node (ref "JP13") (pin "1") (pinfunction "1_1") (pintype "passive"))
      (node (ref "JP3") (pin "1") (pinfunction "1_1") (pintype "passive"))
      (node (ref "RN4") (pin "1") (pinfunction "1_1") (pintype "passive"))
      (node (ref "RN5") (pin "9") (pinfunction "9_9") (pintype "passive"))
    )
    (net (code "117") (name "Net-(JP14-Pad1)") (class "Default")
      (node (ref "JP14") (pin "1") (pinfunction "1_1") (pintype "passive"))
      (node (ref "JP2") (pin "1") (pinfunction "1_1") (pintype "passive"))
      (node (ref "RN1") (pin "1") (pinfunction "1_1") (pintype "passive"))
      (node (ref "RN2") (pin "9") (pinfunction "9_9") (pintype "passive"))
    )
    (net (code "118") (name "Net-(Q1-G)") (class "Default")
      (node (ref "Q1") (pin "1") (pinfunction "G_1") (pintype "passive"))
      (node (ref "R3") (pin "2") (pinfunction "2_2") (pintype "passive"))
    )
    (net (code "119") (name "Net-(Q2-G)") (class "Default")
      (node (ref "Q2") (pin "1") (pinfunction "G_1") (pintype "passive"))
      (node (ref "R4") (pin "2") (pinfunction "2_2") (pintype "passive"))
    )
    (net (code "120") (name "Net-(Q3-G)") (class "Default")
      (node (ref "Q3") (pin "1") (pinfunction "G_1") (pintype "passive"))
      (node (ref "R5") (pin "2") (pinfunction "2_2") (pintype "passive"))
    )
    (net (code "121") (name "Net-(Q4-G)") (class "Default")
      (node (ref "Q4") (pin "1") (pinfunction "G_1") (pintype "passive"))
      (node (ref "R6") (pin "2") (pinfunction "2_2") (pintype "passive"))
    )
    (net (code "122") (name "Net-(Q5-G)") (class "Default")
      (node (ref "Q5") (pin "1") (pinfunction "G_1") (pintype "passive"))
      (node (ref "R7") (pin "2") (pinfunction "2_2") (pintype "passive"))
    )
    (net (code "123") (name "Net-(Q6-G)") (class "Default")
      (node (ref "Q6") (pin "1") (pinfunction "G_1") (pintype "passive"))
      (node (ref "R8") (pin "2") (pinfunction "2_2") (pintype "passive"))
    )
    (net (code "124") (name "Net-(Q7-G)") (class "Default")
      (node (ref "Q7") (pin "1") (pinfunction "G_1") (pintype "passive"))
      (node (ref "R9") (pin "2") (pinfunction "2_2") (pintype "passive"))
    )
    (net (code "125") (name "Net-(Q8-G)") (class "Default")
      (node (ref "Q8") (pin "1") (pinfunction "G_1") (pintype "passive"))
      (node (ref "R10") (pin "2") (pinfunction "2_2") (pintype "passive"))
    )
    (net (code "126") (name "Net-(Q9-G)") (class "Default")
      (node (ref "Q9") (pin "1") (pinfunction "G_1") (pintype "passive"))
      (node (ref "R11") (pin "2") (pinfunction "2_2") (pintype "passive"))
    )
    (net (code "127") (name "Net-(Q10-G)") (class "Default")
      (node (ref "Q10") (pin "1") (pinfunction "G_1") (pintype "passive"))
      (node (ref "R12") (pin "2") (pinfunction "2_2") (pintype "passive"))
    )
    (net (code "128") (name "Net-(Q11-G)") (class "Default")
      (node (ref "Q11") (pin "1") (pinfunction "G_1") (pintype "passive"))
      (node (ref "R13") (pin "2") (pinfunction "2_2") (pintype "passive"))
    )
    (net (code "129") (name "Net-(Q12-G)") (class "Default")
      (node (ref "Q12") (pin "1") (pinfunction "G_1") (pintype "passive"))
      (node (ref "R14") (pin "2") (pinfunction "2_2") (pintype "passive"))
    )
    (net (code "130") (name "Net-(Q13-G)") (class "Default")
      (node (ref "Q13") (pin "1") (pinfunction "G_1") (pintype "passive"))
      (node (ref "R15") (pin "2") (pinfunction "2_2") (pintype "passive"))
    )
    (net (code "131") (name "Net-(Q14-G)") (class "Default")
      (node (ref "Q14") (pin "1") (pinfunction "G_1") (pintype "passive"))
      (node (ref "R16") (pin "2") (pinfunction "2_2") (pintype "passive"))
    )
    (net (code "132") (name "Net-(Q15-G)") (class "Default")
      (node (ref "Q15") (pin "1") (pinfunction "G_1") (pintype "passive"))
      (node (ref "R17") (pin "2") (pinfunction "2_2") (pintype "passive"))
    )
    (net (code "133") (name "Net-(Q16-G)") (class "Default")
      (node (ref "Q16") (pin "1") (pinfunction "G_1") (pintype "passive"))
      (node (ref "R18") (pin "2") (pinfunction "2_2") (pintype "passive"))
    )
    (net (code "134") (name "Net-(RN1B-1)") (class "Default")
      (node (ref "JP14") (pin "2") (pinfunction "2_2") (pintype "passive"))
      (node (ref "JP2") (pin "2") (pinfunction "2_2") (pintype "passive"))
      (node (ref "RN1") (pin "2") (pinfunction "1_2") (pintype "passive"))
      (node (ref "RN2") (pin "8") (pinfunction "8_8") (pintype "passive"))
    )
    (net (code "135") (name "Net-(RN1C-1)") (class "Default")
      (node (ref "JP14") (pin "3") (pinfunction "3_3") (pintype "passive"))
      (node (ref "JP2") (pin "3") (pinfunction "3_3") (pintype "passive"))
      (node (ref "RN1") (pin "3") (pinfunction "1_3") (pintype "passive"))
      (node (ref "RN2") (pin "7") (pinfunction "7_7") (pintype "passive"))
    )
    (net (code "136") (name "Net-(RN1D-1)") (class "Default")
      (node (ref "JP14") (pin "4") (pinfunction "4_4") (pintype "passive"))
      (node (ref "JP2") (pin "4") (pinfunction "4_4") (pintype "passive"))
      (node (ref "RN1") (pin "4") (pinfunction "1_4") (pintype "passive"))
      (node (ref "RN2") (pin "6") (pinfunction "6_6") (pintype "passive"))
    )
    (net (code "137") (name "Net-(RN1E-1)") (class "Default")
      (node (ref "JP14") (pin "7") (pinfunction "7_7") (pintype "passive"))
      (node (ref "JP2") (pin "5") (pinfunction "5_5") (pintype "passive"))
      (node (ref "RN1") (pin "5") (pinfunction "1_5") (pintype "passive"))
      (node (ref "RN2") (pin "5") (pinfunction "5_5") (pintype "passive"))
    )
    (net (code "138") (name "Net-(RN1F-1)") (class "Default")
      (node (ref "JP14") (pin "8") (pinfunction "8_8") (pintype "passive"))
      (node (ref "JP2") (pin "6") (pinfunction "6_6") (pintype "passive"))
      (node (ref "RN1") (pin "6") (pinfunction "1_6") (pintype "passive"))
      (node (ref "RN2") (pin "4") (pinfunction "4_4") (pintype "passive"))
    )
    (net (code "139") (name "Net-(RN1G-1)") (class "Default")
      (node (ref "JP14") (pin "9") (pinfunction "9_9") (pintype "passive"))
      (node (ref "JP2") (pin "7") (pinfunction "7_7") (pintype "passive"))
      (node (ref "RN1") (pin "7") (pinfunction "1_7") (pintype "passive"))
      (node (ref "RN2") (pin "3") (pinfunction "3_3") (pintype "passive"))
    )
    (net (code "140") (name "Net-(RN1H-1)") (class "Default")
      (node (ref "JP14") (pin "10") (pinfunction "10_10") (pintype "passive"))
      (node (ref "JP2") (pin "8") (pinfunction "8_8") (pintype "passive"))
      (node (ref "RN1") (pin "8") (pinfunction "1_8") (pintype "passive"))
      (node (ref "RN2") (pin "2") (pinfunction "2_2") (pintype "passive"))
    )
    (net (code "141") (name "Net-(RN4B-1)") (class "Default")
      (node (ref "JP13") (pin "2") (pinfunction "2_2") (pintype "passive"))
      (node (ref "JP3") (pin "2") (pinfunction "2_2") (pintype "passive"))
      (node (ref "RN4") (pin "2") (pinfunction "1_2") (pintype "passive"))
      (node (ref "RN5") (pin "8") (pinfunction "8_8") (pintype "passive"))
    )
    (net (code "142") (name "Net-(RN4C-1)") (class "Default")
      (node (ref "JP13") (pin "3") (pinfunction "3_3") (pintype "passive"))
      (node (ref "JP3") (pin "3") (pinfunction "3_3") (pintype "passive"))
      (node (ref "RN4") (pin "3") (pinfunction "1_3") (pintype "passive"))
      (node (ref "RN5") (pin "7") (pinfunction "7_7") (pintype "passive"))
    )
    (net (code "143") (name "Net-(RN4D-1)") (class "Default")
      (node (ref "JP13") (pin "4") (pinfunction "4_4") (pintype "passive"))
      (node (ref "JP3") (pin "4") (pinfunction "4_4") (pintype "passive"))
      (node (ref "RN4") (pin "4") (pinfunction "1_4") (pintype "passive"))
      (node (ref "RN5") (pin "6") (pinfunction "6_6") (pintype "passive"))
    )
    (net (code "144") (name "Net-(RN4E-1)") (class "Default")
      (node (ref "JP13") (pin "7") (pinfunction "7_7") (pintype "passive"))
      (node (ref "JP3") (pin "5") (pinfunction "5_5") (pintype "passive"))
      (node (ref "RN4") (pin "5") (pinfunction "1_5") (pintype "passive"))
      (node (ref "RN5") (pin "5") (pinfunction "5_5") (pintype "passive"))
    )
    (net (code "145") (name "Net-(RN4F-1)") (class "Default")
      (node (ref "JP13") (pin "8") (pinfunction "8_8") (pintype "passive"))
      (node (ref "JP3") (pin "6") (pinfunction "6_6") (pintype "passive"))
      (node (ref "RN4") (pin "6") (pinfunction "1_6") (pintype "passive"))
      (node (ref "RN5") (pin "4") (pinfunction "4_4") (pintype "passive"))
    )
    (net (code "146") (name "Net-(RN4G-1)") (class "Default")
      (node (ref "JP13") (pin "9") (pinfunction "9_9") (pintype "passive"))
      (node (ref "JP3") (pin "7") (pinfunction "7_7") (pintype "passive"))
      (node (ref "RN4") (pin "7") (pinfunction "1_7") (pintype "passive"))
      (node (ref "RN5") (pin "3") (pinfunction "3_3") (pintype "passive"))
    )
    (net (code "147") (name "Net-(RN4H-1)") (class "Default")
      (node (ref "JP13") (pin "10") (pinfunction "10_10") (pintype "passive"))
      (node (ref "JP3") (pin "8") (pinfunction "8_8") (pintype "passive"))
      (node (ref "RN4") (pin "8") (pinfunction "1_8") (pintype "passive"))
      (node (ref "RN5") (pin "2") (pinfunction "2_2") (pintype "passive"))
    )
    (net (code "148") (name "OLAT") (class "Default")
      (node (ref "IC3") (pin "12") (pinfunction "RCK_12") (pintype "input"))
      (node (ref "IC5") (pin "12") (pinfunction "RCK_12") (pintype "input"))
      (node (ref "R21") (pin "1") (pinfunction "1_1") (pintype "passive"))
      (node (ref "U$1") (pin "PA8") (pinfunction "PA8_PA8") (pintype "bidirectional"))
    )
    (net (code "149") (name "SCK") (class "Default")
      (node (ref "IC1") (pin "7") (pinfunction "CLK_7") (pintype "input"))
      (node (ref "IC3") (pin "11") (pinfunction "SCK_11") (pintype "input"))
      (node (ref "IC4") (pin "7") (pinfunction "CLK_7") (pintype "input"))
      (node (ref "IC5") (pin "11") (pinfunction "SCK_11") (pintype "input"))
      (node (ref "R19") (pin "1") (pinfunction "1_1") (pintype "passive"))
      (node (ref "U$1") (pin "PB3") (pinfunction "PB3_PB3") (pintype "bidirectional"))
    )
    (net (code "150") (name "SLNK1") (class "Default")
      (node (ref "IC3") (pin "14") (pinfunction "SER_14") (pintype "input"))
      (node (ref "IC5") (pin "9") (pinfunction "QH*_9") (pintype "tri_state"))
    )
    (net (code "151") (name "unconnected-(H1-MOUNT-PadB3,3)") (class "Default")
      (node (ref "H1") (pin "B3,3") (pinfunction "MOUNT_B3,3") (pintype "passive"))
    )
    (net (code "152") (name "unconnected-(H2-MOUNT-PadB3,3)") (class "Default")
      (node (ref "H2") (pin "B3,3") (pinfunction "MOUNT_B3,3") (pintype "passive"))
    )
    (net (code "153") (name "unconnected-(H3-MOUNT-PadB3,3)") (class "Default")
      (node (ref "H3") (pin "B3,3") (pinfunction "MOUNT_B3,3") (pintype "passive"))
    )
    (net (code "154") (name "unconnected-(H4-MOUNT-PadB3,3)") (class "Default")
      (node (ref "H4") (pin "B3,3") (pinfunction "MOUNT_B3,3") (pintype "passive"))
    )
    (net (code "155") (name "unconnected-(IC3A-QH*-Pad9)") (class "Default")
      (node (ref "IC3") (pin "9") (pinfunction "QH*_9") (pintype "tri_state"))
    )
    (net (code "156") (name "unconnected-(IC7-RS-Pad8)") (class "Default")
      (node (ref "IC7") (pin "8") (pinfunction "RS_8") (pintype "input"))
    )
    (net (code "157") (name "unconnected-(IC7-VREF-Pad5)") (class "Default")
      (node (ref "IC7") (pin "5") (pinfunction "VREF_5") (pintype "output"))
    )
    (net (code "158") (name "unconnected-(J3-Pad2)") (class "Default")
      (node (ref "J3") (pin "2") (pinfunction "2_2") (pintype "passive"))
    )
    (net (code "159") (name "unconnected-(JP7-Pad1)") (class "Default")
      (node (ref "JP7") (pin "1") (pinfunction "1_1") (pintype "passive"))
    )
    (net (code "160") (name "unconnected-(JP7-Pad2)") (class "Default")
      (node (ref "JP7") (pin "2") (pinfunction "2_2") (pintype "passive"))
    )
    (net (code "161") (name "unconnected-(JP7-Pad3)") (class "Default")
      (node (ref "JP7") (pin "3") (pinfunction "3_3") (pintype "passive"))
    )
    (net (code "162") (name "unconnected-(JP7-Pad4)") (class "Default")
      (node (ref "JP7") (pin "4") (pinfunction "4_4") (pintype "passive"))
    )
    (net (code "163") (name "unconnected-(JP7-Pad5)") (class "Default")
      (node (ref "JP7") (pin "5") (pinfunction "5_5") (pintype "passive"))
    )
    (net (code "164") (name "unconnected-(JP7-Pad6)") (class "Default")
      (node (ref "JP7") (pin "6") (pinfunction "6_6") (pintype "passive"))
    )
    (net (code "165") (name "unconnected-(JP8-Pad1)") (class "Default")
      (node (ref "JP8") (pin "1") (pinfunction "1_1") (pintype "passive"))
    )
    (net (code "166") (name "unconnected-(JP8-Pad2)") (class "Default")
      (node (ref "JP8") (pin "2") (pinfunction "2_2") (pintype "passive"))
    )
    (net (code "167") (name "unconnected-(JP8-Pad3)") (class "Default")
      (node (ref "JP8") (pin "3") (pinfunction "3_3") (pintype "passive"))
    )
    (net (code "168") (name "unconnected-(JP8-Pad4)") (class "Default")
      (node (ref "JP8") (pin "4") (pinfunction "4_4") (pintype "passive"))
    )
    (net (code "169") (name "unconnected-(JP9-Pad1)") (class "Default")
      (node (ref "JP9") (pin "1") (pinfunction "1_1") (pintype "passive"))
    )
    (net (code "170") (name "unconnected-(JP9-Pad2)") (class "Default")
      (node (ref "JP9") (pin "2") (pinfunction "2_2") (pintype "passive"))
    )
    (net (code "171") (name "unconnected-(JP9-Pad3)") (class "Default")
      (node (ref "JP9") (pin "3") (pinfunction "3_3") (pintype "passive"))
    )
    (net (code "172") (name "unconnected-(JP9-Pad4)") (class "Default")
      (node (ref "JP9") (pin "4") (pinfunction "4_4") (pintype "passive"))
    )
    (net (code "173") (name "unconnected-(JP10-Pad1)") (class "Default")
      (node (ref "JP10") (pin "1") (pinfunction "1_1") (pintype "passive"))
    )
    (net (code "174") (name "unconnected-(JP10-Pad2)") (class "Default")
      (node (ref "JP10") (pin "2") (pinfunction "2_2") (pintype "passive"))
    )
    (net (code "175") (name "unconnected-(JP10-Pad3)") (class "Default")
      (node (ref "JP10") (pin "3") (pinfunction "3_3") (pintype "passive"))
    )
    (net (code "176") (name "unconnected-(JP10-Pad4)") (class "Default")
      (node (ref "JP10") (pin "4") (pinfunction "4_4") (pintype "passive"))
    )
    (net (code "177") (name "unconnected-(JP11-Pad1)") (class "Default")
      (node (ref "JP11") (pin "1") (pinfunction "1_1") (pintype "passive"))
    )
    (net (code "178") (name "unconnected-(JP11-Pad2)") (class "Default")
      (node (ref "JP11") (pin "2") (pinfunction "2_2") (pintype "passive"))
    )
    (net (code "179") (name "unconnected-(JP11-Pad3)") (class "Default")
      (node (ref "JP11") (pin "3") (pinfunction "3_3") (pintype "passive"))
    )
    (net (code "180") (name "unconnected-(JP11-Pad4)") (class "Default")
      (node (ref "JP11") (pin "4") (pinfunction "4_4") (pintype "passive"))
    )
    (net (code "181") (name "unconnected-(JP11-Pad5)") (class "Default")
      (node (ref "JP11") (pin "5") (pinfunction "5_5") (pintype "passive"))
    )
    (net (code "182") (name "unconnected-(JP11-Pad6)") (class "Default")
      (node (ref "JP11") (pin "6") (pinfunction "6_6") (pintype "passive"))
    )
    (net (code "183") (name "unconnected-(JP13-Pad5)") (class "Default")
      (node (ref "JP13") (pin "5") (pinfunction "5_5") (pintype "passive"))
    )
    (net (code "184") (name "unconnected-(JP13-Pad6)") (class "Default")
      (node (ref "JP13") (pin "6") (pinfunction "6_6") (pintype "passive"))
    )
    (net (code "185") (name "unconnected-(JP14-Pad5)") (class "Default")
      (node (ref "JP14") (pin "5") (pinfunction "5_5") (pintype "passive"))
    )
    (net (code "186") (name "unconnected-(JP14-Pad6)") (class "Default")
      (node (ref "JP14") (pin "6") (pinfunction "6_6") (pintype "passive"))
    )
    (net (code "187") (name "unconnected-(JP15-Pad5)") (class "Default")
      (node (ref "JP15") (pin "5") (pinfunction "5_5") (pintype "passive"))
    )
    (net (code "188") (name "unconnected-(JP15-Pad6)") (class "Default")
      (node (ref "JP15") (pin "6") (pinfunction "6_6") (pintype "passive"))
    )
    (net (code "189") (name "unconnected-(U$1-PadBOOT0)") (class "Default")
      (node (ref "U$1") (pin "BOOT0") (pinfunction "BOOT0_BOOT0") (pintype "bidirectional"))
    )
    (net (code "190") (name "unconnected-(U$1-PadIOREF2)") (class "Default")
      (node (ref "U$1") (pin "IOREF2") (pinfunction "IOREF2_IOREF2") (pintype "input"))
    )
    (net (code "191") (name "unconnected-(U$1-PadNC1-PF7)") (class "Default")
      (node (ref "U$1") (pin "NC1-PF7") (pinfunction "NC1-PF7_NC1-PF7") (pintype "bidirectional"))
    )
    (net (code "192") (name "unconnected-(U$1-PadNC2-PF6)") (class "Default")
      (node (ref "U$1") (pin "NC2-PF6") (pinfunction "NC2-PF6_NC2-PF6") (pintype "bidirectional"))
    )
    (net (code "193") (name "unconnected-(U$1-PadNC3)") (class "Default")
      (node (ref "U$1") (pin "NC3") (pinfunction "NC3_NC3") (pintype "no_connect"))
    )
    (net (code "194") (name "unconnected-(U$1-PadNC4)") (class "Default")
      (node (ref "U$1") (pin "NC4") (pinfunction "NC4_NC4") (pintype "no_connect"))
    )
    (net (code "195") (name "unconnected-(U$1-PadNC5-PD8)") (class "Default")
      (node (ref "U$1") (pin "NC5-PD8") (pinfunction "NC5-PD8_NC5-PD8") (pintype "bidirectional"))
    )
    (net (code "196") (name "unconnected-(U$1-PadNC6-PB11)") (class "Default")
      (node (ref "U$1") (pin "NC6-PB11") (pinfunction "NC6-PB11_NC6-PB11") (pintype "no_connect"))
    )
    (net (code "197") (name "unconnected-(U$1-PadNC7-PF5)") (class "Default")
      (node (ref "U$1") (pin "NC7-PF5") (pinfunction "NC7-PF5_NC7-PF5") (pintype "bidirectional"))
    )
    (net (code "198") (name "unconnected-(U$1-PadNC8-PF4)") (class "Default")
      (node (ref "U$1") (pin "NC8-PF4") (pinfunction "NC8-PF4_NC8-PF4") (pintype "bidirectional"))
    )
    (net (code "199") (name "unconnected-(U$1-PadNRESET)") (class "Default")
      (node (ref "U$1") (pin "NRESET") (pinfunction "NRESET_NRESET") (pintype "input"))
    )
    (net (code "200") (name "unconnected-(U$1-PadPA1)") (class "Default")
      (node (ref "U$1") (pin "PA1") (pinfunction "PA1_PA1") (pintype "bidirectional"))
    )
    (net (code "201") (name "unconnected-(U$1-PadPA2)") (class "Default")
      (node (ref "U$1") (pin "PA2") (pinfunction "PA2_PA2") (pintype "bidirectional"))
    )
    (net (code "202") (name "unconnected-(U$1-PadPA3)") (class "Default")
      (node (ref "U$1") (pin "PA3") (pinfunction "PA3_PA3") (pintype "bidirectional"))
    )
    (net (code "203") (name "unconnected-(U$1-PadPA5)") (class "Default")
      (node (ref "U$1") (pin "PA5") (pinfunction "PA5_PA5") (pintype "bidirectional"))
    )
    (net (code "204") (name "unconnected-(U$1-PadPA7)") (class "Default")
      (node (ref "U$1") (pin "PA7") (pinfunction "PA7_PA7") (pintype "bidirectional"))
    )
    (net (code "205") (name "unconnected-(U$1-PadPA9)") (class "Default")
      (node (ref "U$1") (pin "PA9") (pinfunction "PA9_PA9") (pintype "bidirectional"))
    )
    (net (code "206") (name "unconnected-(U$1-PadPA10)") (class "Default")
      (node (ref "U$1") (pin "PA10") (pinfunction "PA10_PA10") (pintype "bidirectional"))
    )
    (net (code "207") (name "unconnected-(U$1-PadPA11)") (class "Default")
      (node (ref "U$1") (pin "PA11") (pinfunction "PA11_PA11") (pintype "bidirectional"))
    )
    (net (code "208") (name "unconnected-(U$1-PadPA12)") (class "Default")
      (node (ref "U$1") (pin "PA12") (pinfunction "PA12_PA12") (pintype "bidirectional"))
    )
    (net (code "209") (name "unconnected-(U$1-PadPA13)") (class "Default")
      (node (ref "U$1") (pin "PA13") (pinfunction "PA13_PA13") (pintype "bidirectional"))
    )
    (net (code "210") (name "unconnected-(U$1-PadPA14)") (class "Default")
      (node (ref "U$1") (pin "PA14") (pinfunction "PA14_PA14") (pintype "bidirectional"))
    )
    (net (code "211") (name "unconnected-(U$1-PadPB0)") (class "Default")
      (node (ref "U$1") (pin "PB0") (pinfunction "PB0_PB0") (pintype "bidirectional"))
    )
    (net (code "212") (name "unconnected-(U$1-PadPB6)") (class "Default")
      (node (ref "U$1") (pin "PB6") (pinfunction "PB6_PB6") (pintype "bidirectional"))
    )
    (net (code "213") (name "unconnected-(U$1-PadPB7)") (class "Default")
      (node (ref "U$1") (pin "PB7") (pinfunction "PB7_PB7") (pintype "bidirectional"))
    )
    (net (code "214") (name "unconnected-(U$1-PadPB13)") (class "Default")
      (node (ref "U$1") (pin "PB13") (pinfunction "PB13_PB13") (pintype "bidirectional"))
    )
    (net (code "215") (name "unconnected-(U$1-PadPB14)") (class "Default")
      (node (ref "U$1") (pin "PB14") (pinfunction "PB14_PB14") (pintype "bidirectional"))
    )
    (net (code "216") (name "unconnected-(U$1-PadPC1)") (class "Default")
      (node (ref "U$1") (pin "PC1") (pinfunction "PC1_PC1") (pintype "bidirectional"))
    )
    (net (code "217") (name "unconnected-(U$1-PadPC4)") (class "Default")
      (node (ref "U$1") (pin "PC4") (pinfunction "PC4_PC4") (pintype "bidirectional"))
    )
    (net (code "218") (name "unconnected-(U$1-PadPC5)") (class "Default")
      (node (ref "U$1") (pin "PC5") (pinfunction "PC5_PC5") (pintype "bidirectional"))
    )
    (net (code "219") (name "unconnected-(U$1-PadPC6)") (class "Default")
      (node (ref "U$1") (pin "PC6") (pinfunction "PC6_PC6") (pintype "bidirectional"))
    )
    (net (code "220") (name "unconnected-(U$1-PadPC7)") (class "Default")
      (node (ref "U$1") (pin "PC7") (pinfunction "PC7_PC7") (pintype "bidirectional"))
    )
    (net (code "221") (name "unconnected-(U$1-PadPC8)") (class "Default")
      (node (ref "U$1") (pin "PC8") (pinfunction "PC8_PC8") (pintype "bidirectional"))
    )
    (net (code "222") (name "unconnected-(U$1-PadPC9)") (class "Default")
      (node (ref "U$1") (pin "PC9") (pinfunction "PC9_PC9") (pintype "bidirectional"))
    )
    (net (code "223") (name "unconnected-(U$1-PadPC13)") (class "Default")
      (node (ref "U$1") (pin "PC13") (pinfunction "PC13_PC13") (pintype "bidirectional"))
    )
    (net (code "224") (name "unconnected-(U$1-PadPC14)") (class "Default")
      (node (ref "U$1") (pin "PC14") (pinfunction "PC14_PC14") (pintype "bidirectional"))
    )
    (net (code "225") (name "unconnected-(U$1-PadPC15)") (class "Default")
      (node (ref "U$1") (pin "PC15") (pinfunction "PC15_PC15") (pintype "bidirectional"))
    )
    (net (code "226") (name "unconnected-(U$1-PadPF0-PH0)") (class "Default")
      (node (ref "U$1") (pin "PF0-PH0") (pinfunction "PF0-PH0_PF0-PH0") (pintype "bidirectional"))
    )
  )
)
